# Sheet_1-copy-copy_2026-03-31.net
KiCad netlist of a schematic drawn in Altium Designer
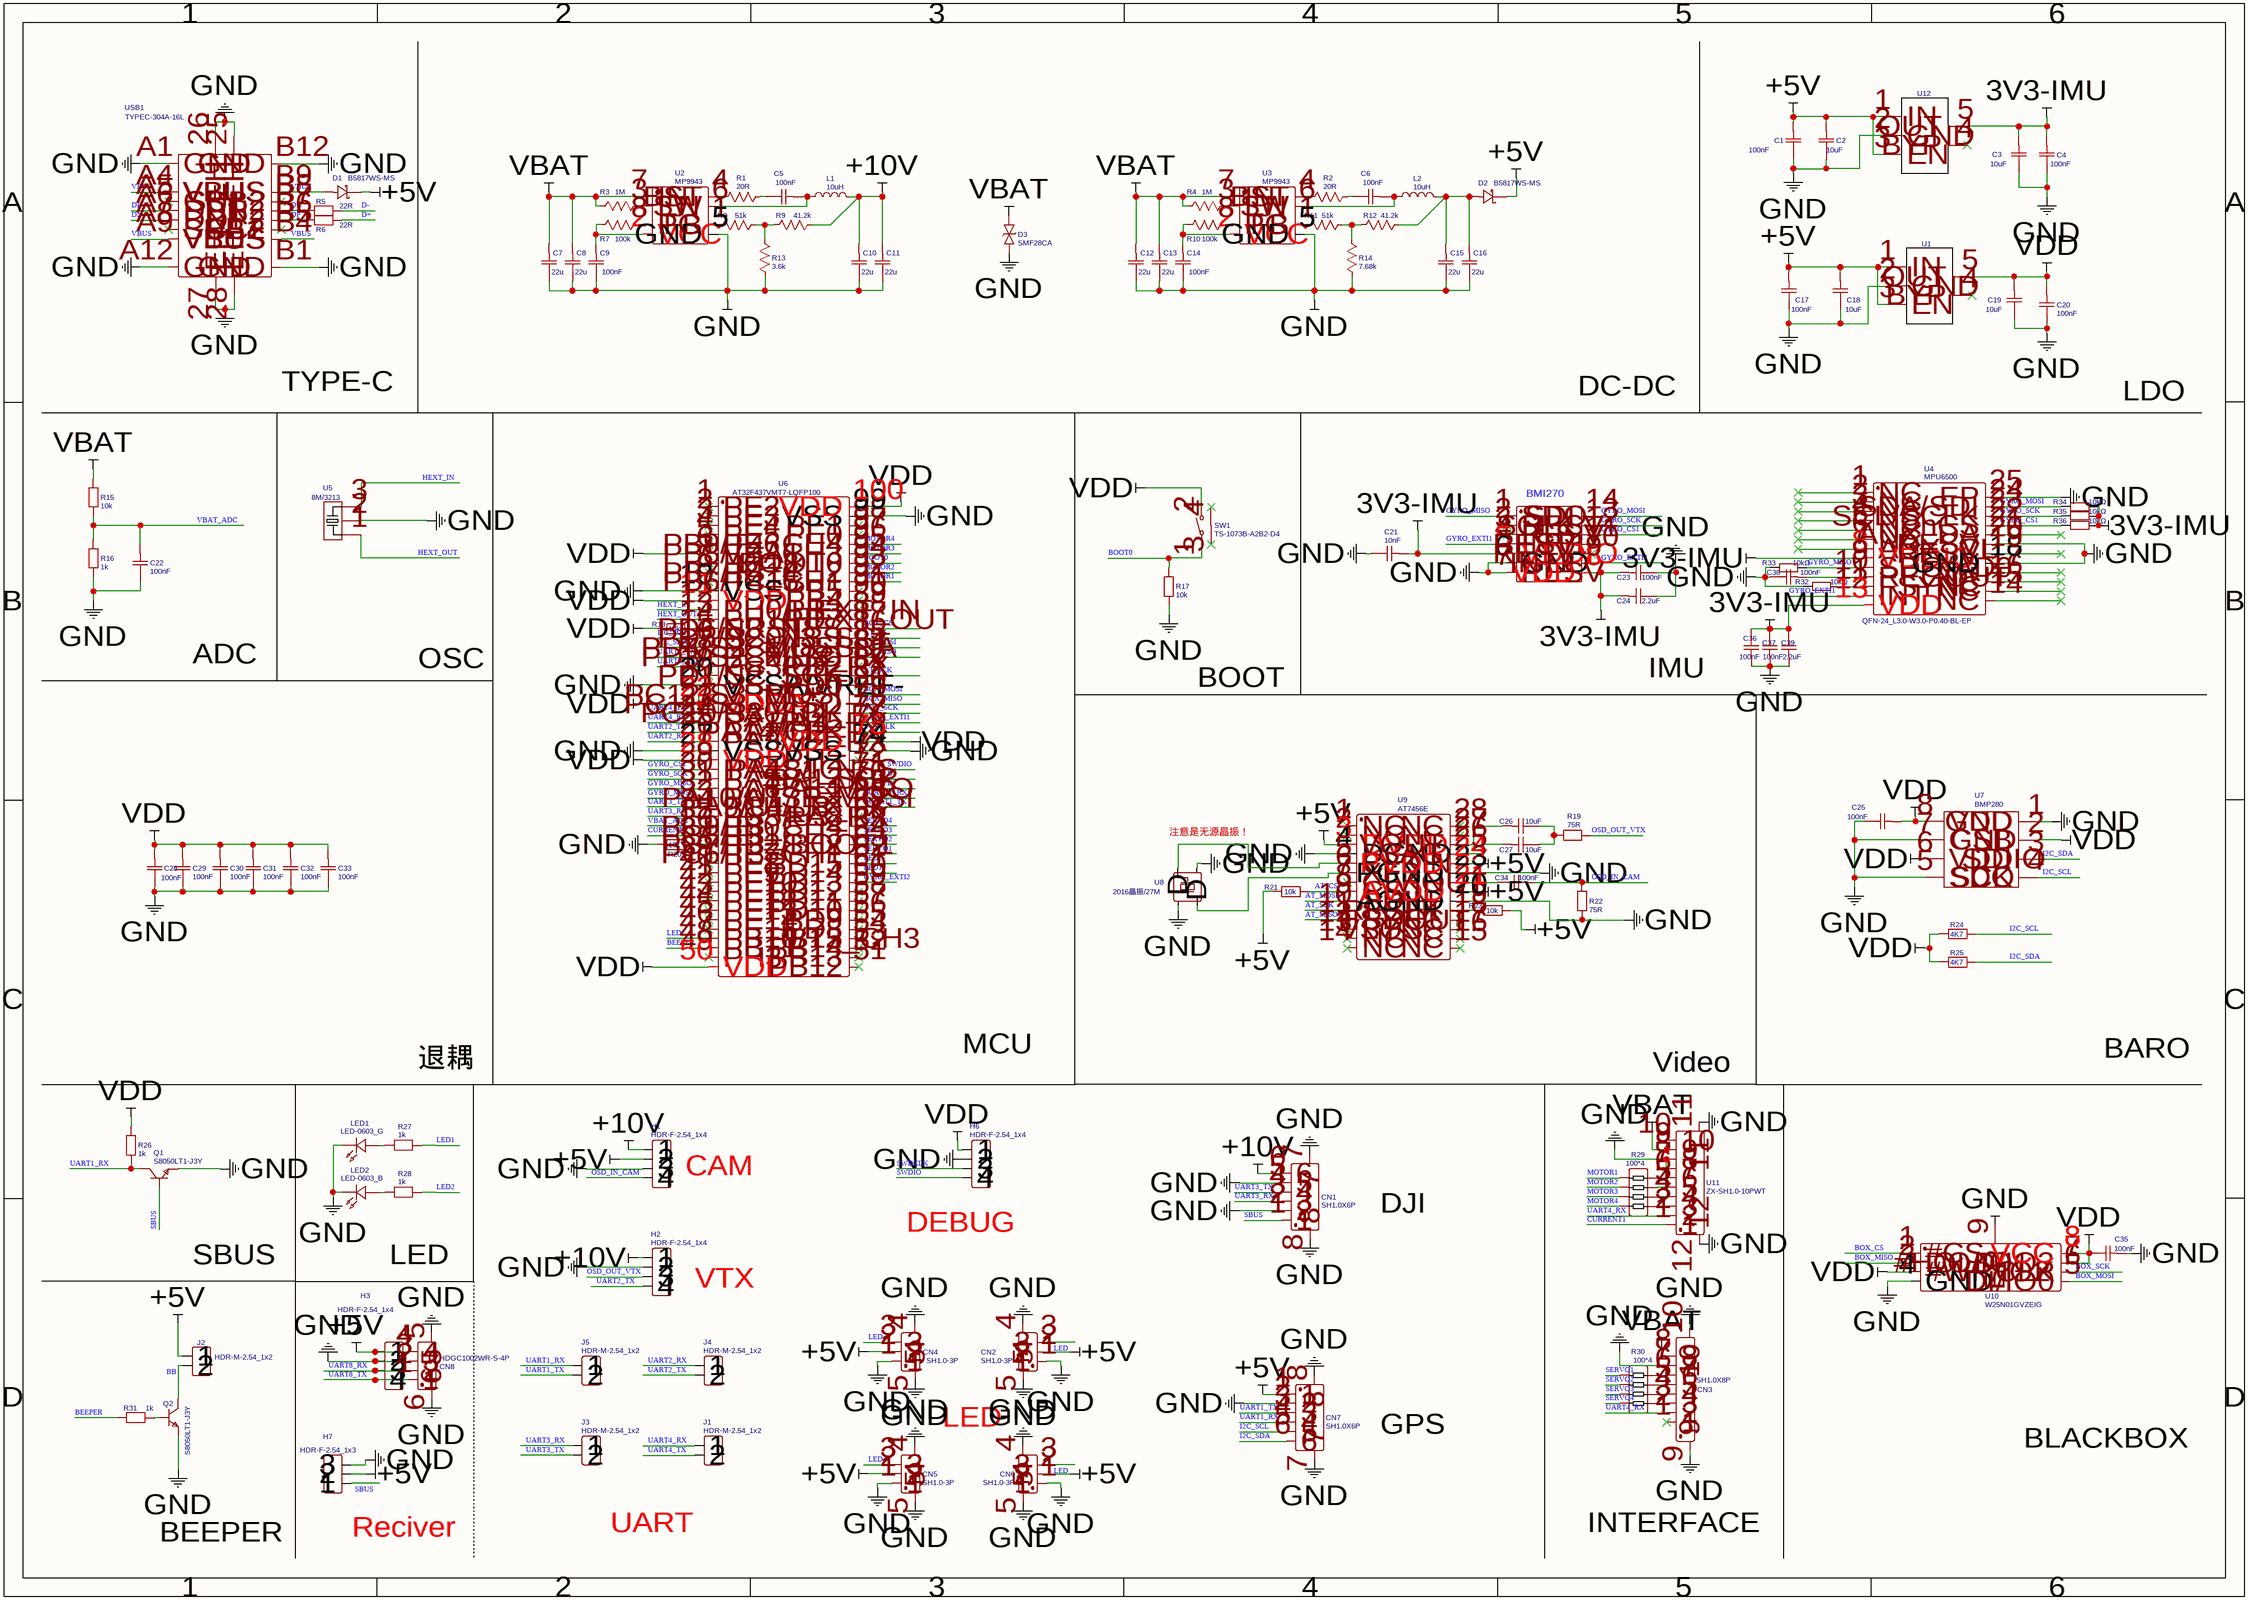
[diagram p0: Sheet_1-copy-copy_2026-03-31.schdoc]

(export (version "E")
  (design (tool "Eeschema 10.0.6"))
  (components
    (comp (ref "C1")
      (value "100nF")
      (fields (field (name "CONTRIBUTOR") "LCEDA_Lib"))
      (libsource (lib "altium-import") (part "root_1_100nF_"))
    )
    (comp (ref "C2")
      (value "10uF")
      (fields (field (name "CONTRIBUTOR") "LCEDA_Lib"))
      (libsource (lib "altium-import") (part "root_1_10uF_"))
    )
    (comp (ref "C3")
      (value "10uF")
      (fields (field (name "CONTRIBUTOR") "LCEDA_Lib"))
      (libsource (lib "altium-import") (part "root_1_10uF_"))
    )
    (comp (ref "C4")
      (value "100nF")
      (fields (field (name "CONTRIBUTOR") "LCEDA_Lib"))
      (libsource (lib "altium-import") (part "root_1_100nF_"))
    )
    (comp (ref "C5")
      (value "100nF")
      (fields (field (name "CONTRIBUTOR") "LCEDA_Lib"))
      (libsource (lib "altium-import") (part "root_0_100nF_"))
    )
    (comp (ref "C6")
      (value "100nF")
      (fields (field (name "CONTRIBUTOR") "LCEDA_Lib"))
      (libsource (lib "altium-import") (part "root_0_100nF_"))
    )
    (comp (ref "C7")
      (value "22u")
      (fields (field (name "CONTRIBUTOR") "LCEDA_Lib"))
      (libsource (lib "altium-import") (part "root_1_22u_"))
    )
    (comp (ref "C8")
      (value "22u")
      (fields (field (name "CONTRIBUTOR") "LCEDA_Lib"))
      (libsource (lib "altium-import") (part "root_1_22u_"))
    )
    (comp (ref "C9")
      (value "100nF")
      (fields (field (name "CONTRIBUTOR") "LCEDA_Lib"))
      (libsource (lib "altium-import") (part "root_1_100nF_"))
    )
    (comp (ref "C10")
      (value "22u")
      (fields (field (name "CONTRIBUTOR") "LCEDA_Lib"))
      (libsource (lib "altium-import") (part "root_1_22u_"))
    )
    (comp (ref "C11")
      (value "22u")
      (fields (field (name "CONTRIBUTOR") "LCEDA_Lib"))
      (libsource (lib "altium-import") (part "root_1_22u_"))
    )
    (comp (ref "C12")
      (value "22u")
      (fields (field (name "CONTRIBUTOR") "LCEDA_Lib"))
      (libsource (lib "altium-import") (part "root_1_22u_"))
    )
    (comp (ref "C13")
      (value "22u")
      (fields (field (name "CONTRIBUTOR") "LCEDA_Lib"))
      (libsource (lib "altium-import") (part "root_1_22u_"))
    )
    (comp (ref "C14")
      (value "100nF")
      (fields (field (name "CONTRIBUTOR") "LCEDA_Lib"))
      (libsource (lib "altium-import") (part "root_1_100nF_"))
    )
    (comp (ref "C15")
      (value "22u")
      (fields (field (name "CONTRIBUTOR") "LCEDA_Lib"))
      (libsource (lib "altium-import") (part "root_1_22u_"))
    )
    (comp (ref "C16")
      (value "22u")
      (fields (field (name "CONTRIBUTOR") "LCEDA_Lib"))
      (libsource (lib "altium-import") (part "root_1_22u_"))
    )
    (comp (ref "C17")
      (value "100nF")
      (fields (field (name "CONTRIBUTOR") "LCEDA_Lib"))
      (libsource (lib "altium-import") (part "root_1_100nF_"))
    )
    (comp (ref "C18")
      (value "10uF")
      (fields (field (name "CONTRIBUTOR") "LCEDA_Lib"))
      (libsource (lib "altium-import") (part "root_1_10uF_"))
    )
    (comp (ref "C19")
      (value "10uF")
      (fields (field (name "CONTRIBUTOR") "LCEDA_Lib"))
      (libsource (lib "altium-import") (part "root_1_10uF_"))
    )
    (comp (ref "C20")
      (value "100nF")
      (fields (field (name "CONTRIBUTOR") "LCEDA_Lib"))
      (libsource (lib "altium-import") (part "root_1_100nF_"))
    )
    (comp (ref "C21")
      (value "10nF")
      (fields (field (name "CONTRIBUTOR") "LCEDA_Lib"))
      (libsource (lib "altium-import") (part "root_0_10nF_"))
    )
    (comp (ref "C22")
      (value "100nF")
      (fields (field (name "CONTRIBUTOR") "LCEDA_Lib"))
      (libsource (lib "altium-import") (part "root_1_100nF_"))
    )
    (comp (ref "C23")
      (value "100nF")
      (fields (field (name "CONTRIBUTOR") "LCEDA_Lib"))
      (libsource (lib "altium-import") (part "root_2_100nF_"))
    )
    (comp (ref "C24")
      (value "2.2uF")
      (fields (field (name "CONTRIBUTOR") "LCEDA_Lib"))
      (libsource (lib "altium-import") (part "root_2_2.2uF_"))
    )
    (comp (ref "C25")
      (value "100nF")
      (fields (field (name "CONTRIBUTOR") "LCEDA_Lib"))
      (libsource (lib "altium-import") (part "root_0_100nF_"))
    )
    (comp (ref "C26")
      (value "10uF")
      (fields (field (name "CONTRIBUTOR") "LCEDA_Lib"))
      (libsource (lib "altium-import") (part "root_2_10uF_"))
    )
    (comp (ref "C27")
      (value "10uF")
      (fields (field (name "CONTRIBUTOR") "LCEDA_Lib"))
      (libsource (lib "altium-import") (part "root_2_10uF_"))
    )
    (comp (ref "C28")
      (value "100nF")
      (fields (field (name "CONTRIBUTOR") "LCEDA_Lib"))
      (libsource (lib "altium-import") (part "root_1_100nF_"))
    )
    (comp (ref "C29")
      (value "100nF")
      (fields (field (name "CONTRIBUTOR") "LCEDA_Lib"))
      (libsource (lib "altium-import") (part "root_1_100nF_"))
    )
    (comp (ref "C30")
      (value "100nF")
      (fields (field (name "CONTRIBUTOR") "LCEDA_Lib"))
      (libsource (lib "altium-import") (part "root_1_100nF_"))
    )
    (comp (ref "C31")
      (value "100nF")
      (fields (field (name "CONTRIBUTOR") "LCEDA_Lib"))
      (libsource (lib "altium-import") (part "root_1_100nF_"))
    )
    (comp (ref "C32")
      (value "100nF")
      (fields (field (name "CONTRIBUTOR") "LCEDA_Lib"))
      (libsource (lib "altium-import") (part "root_1_100nF_"))
    )
    (comp (ref "C33")
      (value "100nF")
      (fields (field (name "CONTRIBUTOR") "LCEDA_Lib"))
      (libsource (lib "altium-import") (part "root_1_100nF_"))
    )
    (comp (ref "C34")
      (value "100nF")
      (fields (field (name "CONTRIBUTOR") "LCEDA_Lib"))
      (libsource (lib "altium-import") (part "root_0_100nF_"))
    )
    (comp (ref "C35")
      (value "100nF")
      (fields (field (name "CONTRIBUTOR") "LCEDA_Lib"))
      (libsource (lib "altium-import") (part "root_0_100nF_"))
    )
    (comp (ref "C36")
      (value "100nF")
      (fields (field (name "CONTRIBUTOR") "LCEDA_Lib"))
      (libsource (lib "altium-import") (part "root_3_100nF_"))
    )
    (comp (ref "C37")
      (value "100nF")
      (fields (field (name "CONTRIBUTOR") "LCEDA_Lib"))
      (libsource (lib "altium-import") (part "root_3_100nF_"))
    )
    (comp (ref "C38")
      (value "100nF")
      (fields (field (name "CONTRIBUTOR") "LCEDA_Lib"))
      (libsource (lib "altium-import") (part "root_0_100nF_"))
    )
    (comp (ref "C39")
      (value "2.2uF")
      (fields (field (name "CONTRIBUTOR") "LCEDA_Lib"))
      (libsource (lib "altium-import") (part "root_3_2.2uF_"))
    )
    (comp (ref "CN1")
      (value "SH1.0X6P")
      (fields
        (field (name "MANUFACTURER") "Megastar(兆星)")
        (field (name "MANUFACTURER PART") "ZX-SH1.0-6PWT")
        (field (name "CONTRIBUTOR") "lcsc")
      )
      (libsource (lib "altium-import") (part "root_0_SH1.0X6P_"))
    )
    (comp (ref "CN2")
      (value "SH1.0-3P")
      (fields
        (field (name "MANUFACTURER") "HDGC(华德共创)")
        (field (name "MANUFACTURER PART") "HDGC1002WR-S-3P")
        (field (name "CONTRIBUTOR") "LCSC")
      )
      (libsource (lib "") (part "root_2_SH1.0-3P__1"))
    )
    (comp (ref "CN3")
      (value "SH1.0X8P")
      (fields (field (name "MANUFACTURER PART") "WAFER_SMT_1.0X8") (field (name "CONTRIBUTOR") "lcsc"))
      (libsource (lib "altium-import") (part "root_0_SH1.0X8P_"))
    )
    (comp (ref "CN4")
      (value "SH1.0-3P")
      (fields
        (field (name "MANUFACTURER") "HDGC(华德共创)")
        (field (name "MANUFACTURER PART") "HDGC1002WR-S-3P")
        (field (name "CONTRIBUTOR") "LCSC")
      )
      (libsource (lib "altium-import") (part "root_2_SH1.0-3P_"))
    )
    (comp (ref "CN5")
      (value "SH1.0-3P")
      (fields
        (field (name "MANUFACTURER") "HDGC(华德共创)")
        (field (name "MANUFACTURER PART") "HDGC1002WR-S-3P")
        (field (name "CONTRIBUTOR") "LCSC")
      )
      (libsource (lib "altium-import") (part "root_0_SH1.0-3P_"))
    )
    (comp (ref "CN6")
      (value "SH1.0-3P")
      (fields
        (field (name "MANUFACTURER") "HDGC(华德共创)")
        (field (name "MANUFACTURER PART") "HDGC1002WR-S-3P")
        (field (name "CONTRIBUTOR") "LCSC")
      )
      (libsource (lib "") (part "root_0_SH1.0-3P__1"))
    )
    (comp (ref "CN7")
      (value "SH1.0X6P")
      (fields
        (field (name "MANUFACTURER") "Megastar(兆星)")
        (field (name "MANUFACTURER PART") "ZX-SH1.0-6PWT")
        (field (name "CONTRIBUTOR") "lcsc")
      )
      (libsource (lib "") (part "root_0_SH1.0X6P__1"))
    )
    (comp (ref "CN8")
      (value "HDGC1002WR-S-4P")
      (fields (field (name "MANUFACTURER") "HDGC(华德共创)") (field (name "CONTRIBUTOR") "LCSC"))
      (libsource (lib "altium-import") (part "root_0_HDGC1002WR-S-4P_"))
    )
    (comp (ref "D1")
      (value "B5817WS-MS")
      (fields (field (name "MANUFACTURER") "MSKSEMI(美森科)") (field (name "CONTRIBUTOR") "LCSC"))
      (libsource (lib "altium-import") (part "root_2_B5817WS-MS_"))
    )
    (comp (ref "D2")
      (value "B5817WS-MS")
      (fields (field (name "MANUFACTURER") "MSKSEMI(美森科)") (field (name "CONTRIBUTOR") "LCSC"))
      (libsource (lib "altium-import") (part "root_2_B5817WS-MS_"))
    )
    (comp (ref "D3")
      (value "SMF28CA")
      (fields (field (name "MANUFACTURER") "AnBon(安邦)") (field (name "CONTRIBUTOR") "LCSC"))
      (libsource (lib "altium-import") (part "root_3_SMF28CA_"))
    )
    (comp (ref "H1")
      (value "HDR-F-2.54_1x4")
      (fields (field (name "CONTRIBUTOR") "LCEDA_Lib"))
      (libsource (lib "altium-import") (part "root_0_HDR-F-2.54_1x4_"))
    )
    (comp (ref "H2")
      (value "HDR-F-2.54_1x4")
      (fields (field (name "CONTRIBUTOR") "LCEDA_Lib"))
      (libsource (lib "altium-import") (part "root_0_HDR-F-2.54_1x4_"))
    )
    (comp (ref "H3")
      (value "HDR-F-2.54_1x4")
      (fields (field (name "CONTRIBUTOR") "LCEDA_Lib"))
      (libsource (lib "altium-import") (part "root_0_HDR-F-2.54_1x4_"))
    )
    (comp (ref "H6")
      (value "HDR-F-2.54_1x4")
      (fields (field (name "CONTRIBUTOR") "LCEDA_Lib"))
      (libsource (lib "altium-import") (part "root_0_HDR-F-2.54_1x4_"))
    )
    (comp (ref "H7")
      (value "HDR-F-2.54_1x3")
      (fields (field (name "CONTRIBUTOR") "LCEDA_Lib"))
      (libsource (lib "altium-import") (part "root_2_HDR-F-2.54_1x3_"))
    )
    (comp (ref "J1")
      (value "HDR-M-2.54_1x2")
      (fields (field (name "CONTRIBUTOR") "LCEDA_Lib"))
      (libsource (lib "altium-import") (part "root_0_HDR-M-2.54_1x2_"))
    )
    (comp (ref "J2")
      (value "HDR-M-2.54_1x2")
      (fields (field (name "CONTRIBUTOR") "LCEDA_Lib"))
      (libsource (lib "altium-import") (part "root_0_HDR-M-2.54_1x2_"))
    )
    (comp (ref "J3")
      (value "HDR-M-2.54_1x2")
      (fields (field (name "CONTRIBUTOR") "LCEDA_Lib"))
      (libsource (lib "altium-import") (part "root_0_HDR-M-2.54_1x2_"))
    )
    (comp (ref "J4")
      (value "HDR-M-2.54_1x2")
      (fields (field (name "CONTRIBUTOR") "LCEDA_Lib"))
      (libsource (lib "altium-import") (part "root_0_HDR-M-2.54_1x2_"))
    )
    (comp (ref "J5")
      (value "HDR-M-2.54_1x2")
      (fields (field (name "CONTRIBUTOR") "LCEDA_Lib"))
      (libsource (lib "altium-import") (part "root_0_HDR-M-2.54_1x2_"))
    )
    (comp (ref "L1")
      (value "10uH")
      (fields
        (field (name "MANUFACTURER") "EMTEK")
        (field (name "MANUFACTURER PART") "PHC0420-100M-T")
        (field (name "CONTRIBUTOR") "LCSC")
      )
      (libsource (lib "altium-import") (part "root_0_10uH_"))
    )
    (comp (ref "L2")
      (value "10uH")
      (fields
        (field (name "MANUFACTURER") "EMTEK")
        (field (name "MANUFACTURER PART") "PHC0420-100M-T")
        (field (name "CONTRIBUTOR") "LCSC")
      )
      (libsource (lib "altium-import") (part "root_0_10uH_"))
    )
    (comp (ref "LED1")
      (value "LED-0603_G")
      (fields
        (field (name "MANUFACTURER") "EVERLIGHT(台湾亿光)")
        (field (name "MANUFACTURER PART") "19-217/GHC-YR1S2/3T")
        (field (name "CONTRIBUTOR") "LCEDA_Lib")
      )
      (libsource (lib "altium-import") (part "root_2_LED-0603_G_"))
    )
    (comp (ref "LED2")
      (value "LED-0603_B")
      (fields
        (field (name "MANUFACTURER") "EVERLIGHT(台湾亿光)")
        (field (name "MANUFACTURER PART") "19-217/BHC-ZL1M2RY/3T")
        (field (name "CONTRIBUTOR") "LCEDA_01")
      )
      (libsource (lib "altium-import") (part "root_2_LED-0603_B_"))
    )
    (comp (ref "Q1")
      (value "S8050LT1-J3Y")
      (fields (field (name "MANUFACTURER") "FH(风华)") (field (name "CONTRIBUTOR") "lcsc"))
      (libsource (lib "altium-import") (part "root_1_S8050LT1-J3Y_"))
    )
    (comp (ref "Q2")
      (value "S8050LT1-J3Y")
      (fields (field (name "MANUFACTURER") "FH(风华)") (field (name "CONTRIBUTOR") "lcsc"))
      (libsource (lib "altium-import") (part "root_0_S8050LT1-J3Y_"))
    )
    (comp (ref "R1")
      (value "20R")
      (fields (field (name "CONTRIBUTOR") "LCEDA_Lib"))
      (libsource (lib "altium-import") (part "root_0_20R_"))
    )
    (comp (ref "R2")
      (value "20R")
      (fields (field (name "CONTRIBUTOR") "LCEDA_Lib"))
      (libsource (lib "altium-import") (part "root_0_20R_"))
    )
    (comp (ref "R3")
      (value "1M")
      (fields (field (name "CONTRIBUTOR") "LCEDA_Lib"))
      (libsource (lib "altium-import") (part "root_2_1M_"))
    )
    (comp (ref "R4")
      (value "1M")
      (fields (field (name "CONTRIBUTOR") "LCEDA_Lib"))
      (libsource (lib "altium-import") (part "root_2_1M_"))
    )
    (comp (ref "R5")
      (value "22R")
      (fields (field (name "CONTRIBUTOR") "LCEDA_Lib"))
      (libsource (lib "altium-import") (part "root_0_22R_"))
    )
    (comp (ref "R6")
      (value "22R")
      (fields (field (name "CONTRIBUTOR") "LCEDA_Lib"))
      (libsource (lib "altium-import") (part "root_0_22R_"))
    )
    (comp (ref "R7")
      (value "100k")
      (fields (field (name "CONTRIBUTOR") "LCEDA_Lib"))
      (libsource (lib "altium-import") (part "root_0_100k_"))
    )
    (comp (ref "R8")
      (value "51k")
      (fields (field (name "CONTRIBUTOR") "LCEDA_Lib"))
      (libsource (lib "altium-import") (part "root_0_51k_"))
    )
    (comp (ref "R9")
      (value "41.2k")
      (fields (field (name "CONTRIBUTOR") "LCEDA_Lib"))
      (libsource (lib "altium-import") (part "root_0_41.2k_"))
    )
    (comp (ref "R10")
      (value "100k")
      (fields (field (name "CONTRIBUTOR") "LCEDA_Lib"))
      (libsource (lib "altium-import") (part "root_0_100k_"))
    )
    (comp (ref "R11")
      (value "51k")
      (fields (field (name "CONTRIBUTOR") "LCEDA_Lib"))
      (libsource (lib "altium-import") (part "root_0_51k_"))
    )
    (comp (ref "R12")
      (value "41.2k")
      (fields (field (name "CONTRIBUTOR") "LCEDA_Lib"))
      (libsource (lib "altium-import") (part "root_0_41.2k_"))
    )
    (comp (ref "R13")
      (value "3.6k")
      (fields (field (name "CONTRIBUTOR") "LCEDA_Lib"))
      (libsource (lib "altium-import") (part "root_1_3.6k_"))
    )
    (comp (ref "R14")
      (value "7.68k")
      (fields (field (name "CONTRIBUTOR") "LCEDA_Lib"))
      (libsource (lib "altium-import") (part "root_1_7.68k_"))
    )
    (comp (ref "R15")
      (value "10k")
      (fields (field (name "CONTRIBUTOR") "LCEDA_Lib"))
      (libsource (lib "altium-import") (part "root_1_10k_"))
    )
    (comp (ref "R16")
      (value "1k")
      (fields (field (name "CONTRIBUTOR") "LCEDA_Lib"))
      (libsource (lib "altium-import") (part "root_1_1k_"))
    )
    (comp (ref "R17")
      (value "10k")
      (fields (field (name "CONTRIBUTOR") "LCEDA_Lib"))
      (libsource (lib "altium-import") (part "root_3_10k_"))
    )
    (comp (ref "R18")
      (value "10k")
      (fields (field (name "CONTRIBUTOR") "LCEDA_Lib"))
      (libsource (lib "altium-import") (part "root_2_10k_"))
    )
    (comp (ref "R19")
      (value "75R")
      (fields (field (name "CONTRIBUTOR") "LCEDA_Lib"))
      (libsource (lib "altium-import") (part "root_0_75R_"))
    )
    (comp (ref "R20")
      (value "10k")
      (fields (field (name "CONTRIBUTOR") "LCEDA_Lib"))
      (libsource (lib "altium-import") (part "root_0_10k_"))
    )
    (comp (ref "R21")
      (value "10k")
      (fields (field (name "CONTRIBUTOR") "LCEDA_Lib"))
      (libsource (lib "altium-import") (part "root_0_10k_"))
    )
    (comp (ref "R22")
      (value "75R")
      (fields (field (name "CONTRIBUTOR") "LCEDA_Lib"))
      (libsource (lib "altium-import") (part "root_1_75R_"))
    )
    (comp (ref "R23")
      (value "10k")
      (fields (field (name "CONTRIBUTOR") "LCEDA_Lib"))
      (libsource (lib "altium-import") (part "root_0_10k_"))
    )
    (comp (ref "R24")
      (value "4K7")
      (fields (field (name "CONTRIBUTOR") "LCEDA_Lib"))
      (libsource (lib "altium-import") (part "root_2_4K7_"))
    )
    (comp (ref "R25")
      (value "4K7")
      (fields (field (name "CONTRIBUTOR") "LCEDA_Lib"))
      (libsource (lib "altium-import") (part "root_2_4K7_"))
    )
    (comp (ref "R26")
      (value "1k")
      (fields (field (name "CONTRIBUTOR") "LCEDA_Lib"))
      (libsource (lib "altium-import") (part "root_1_1k_"))
    )
    (comp (ref "R27")
      (value "1k")
      (fields (field (name "CONTRIBUTOR") "LCEDA_Lib"))
      (libsource (lib "altium-import") (part "root_0_1k_"))
    )
    (comp (ref "R28")
      (value "1k")
      (fields (field (name "CONTRIBUTOR") "LCEDA_Lib"))
      (libsource (lib "altium-import") (part "root_0_1k_"))
    )
    (comp (ref "R29")
      (value "100*4")
      (fields
        (field (name "MANUFACTURER") "UNI-ROYAL(厚声)")
        (field (name "MANUFACTURER PART") "4D02WGF1002TCE")
        (field (name "CONTRIBUTOR") "LCSC")
      )
      (libsource (lib "altium-import") (part "root_2_100*4_"))
    )
    (comp (ref "R30")
      (value "100*4")
      (fields
        (field (name "MANUFACTURER") "UNI-ROYAL(厚声)")
        (field (name "MANUFACTURER PART") "4D02WGF1002TCE")
        (field (name "CONTRIBUTOR") "LCSC")
      )
      (libsource (lib "altium-import") (part "root_2_100*4_"))
    )
    (comp (ref "R31")
      (value "1k")
      (fields (field (name "CONTRIBUTOR") "LCEDA_Lib"))
      (libsource (lib "altium-import") (part "root_0_1k_"))
    )
    (comp (ref "R32")
      (value "10kΩ")
      (fields (field (name "MANUFACTURER") "YAGEO(国巨)") (field (name "MANUFACTURER PART") "RC0402FR-0710KL"))
      (libsource (lib "altium-import") (part "root_0_10kΩ_"))
    )
    (comp (ref "R33")
      (value "10kΩ")
      (fields (field (name "MANUFACTURER") "YAGEO(国巨)") (field (name "MANUFACTURER PART") "RC0402FR-0710KL"))
      (libsource (lib "altium-import") (part "root_0_10kΩ_"))
    )
    (comp (ref "R34")
      (value "10kΩ")
      (fields (field (name "MANUFACTURER") "YAGEO(国巨)") (field (name "MANUFACTURER PART") "RC0402FR-0710KL"))
      (libsource (lib "altium-import") (part "root_0_10kΩ_"))
    )
    (comp (ref "R35")
      (value "10kΩ")
      (fields (field (name "MANUFACTURER") "YAGEO(国巨)") (field (name "MANUFACTURER PART") "RC0402FR-0710KL"))
      (libsource (lib "altium-import") (part "root_0_10kΩ_"))
    )
    (comp (ref "R36")
      (value "10kΩ")
      (fields (field (name "MANUFACTURER") "YAGEO(国巨)") (field (name "MANUFACTURER PART") "RC0402FR-0710KL"))
      (libsource (lib "altium-import") (part "root_0_10kΩ_"))
    )
    (comp (ref "SDO1")
      (value "BMI270")
      (fields (field (name "CONTRIBUTOR") "SPRain"))
      (libsource (lib "altium-import") (part "root_0_BMI270_"))
    )
    (comp (ref "SW1")
      (value "TS-1073B-A2B2-D4")
      (fields (field (name "MANUFACTURER") "Yuandi(元迪)") (field (name "CONTRIBUTOR") "LCSC"))
      (libsource (lib "altium-import") (part "root_1_TS-1073B-A2B2-D4_"))
    )
    (comp (ref "U1")
      (value "SPX3819M5-L-3-3/TR")
      (fields (field (name "MANUFACTURER") "MaxLinear(迈凌)"))
      (libsource (lib "altium-import") (part "root_0_SPX3819M5-L-3-3/TR_"))
    )
    (comp (ref "U2")
      (value "MP9943")
      (fields (field (name "CONTRIBUTOR") "jeasyn"))
      (libsource (lib "altium-import") (part "root_0_MP9943_"))
    )
    (comp (ref "U3")
      (value "MP9943")
      (fields (field (name "CONTRIBUTOR") "jeasyn"))
      (libsource (lib "altium-import") (part "root_0_MP9943_"))
    )
    (comp (ref "U4")
      (value "MPU6500")
      (fields
        (field (name "MANUFACTURER") "TDK InvenSense(应美盛)")
        (field (name "MANUFACTURER PART") "MPU-6500")
      )
      (libsource (lib "altium-import") (part "root_0_MPU6500_"))
    )
    (comp (ref "U5")
      (value "8M/3213")
      (fields (field (name "CONTRIBUTOR") "5_6956"))
      (libsource (lib "altium-import") (part "root_1_8M/3213_"))
    )
    (comp (ref "U6")
      (value "AT32F437VMT7-LQFP100")
      (fields
        (field (name "MANUFACTURER") "ARTERY（雅特力）")
        (field (name "MANUFACTURER PART") "AT32F435VMT7")
        (field (name "CONTRIBUTOR") "lcsc")
      )
      (libsource (lib "altium-import") (part "root_0_AT32F437VMT7-LQFP100_"))
    )
    (comp (ref "U7")
      (value "BMP280")
      (fields (field (name "MANUFACTURER") "Bosch"))
      (libsource (lib "altium-import") (part "root_0_BMP280_"))
    )
    (comp (ref "U8")
      (value "2016晶振/27M")
      (fields (field (name "CONTRIBUTOR") "jimssa"))
      (libsource (lib "altium-import") (part "root_2_2016晶振/27M_"))
    )
    (comp (ref "U9")
      (value "AT7456E")
      (fields (field (name "MANUFACTURER") "ZHONGKEWEI"))
      (libsource (lib "altium-import") (part "root_0_AT7456E_"))
    )
    (comp (ref "U10")
      (value "W25N01GVZEIG")
      (fields (field (name "MANUFACTURER") "Winbond Elec") (field (name "CONTRIBUTOR") "SudoMaker"))
      (libsource (lib "altium-import") (part "root_0_W25N01GVZEIG_"))
    )
    (comp (ref "U11")
      (value "ZX-SH1.0-10PWT")
      (fields (field (name "MANUFACTURER") "Megastar(兆星)") (field (name "CONTRIBUTOR") "lcsc"))
      (libsource (lib "altium-import") (part "root_0_ZX-SH1.0-10PWT_"))
    )
    (comp (ref "U12")
      (value "SPX3819M5-L-3-3/TR")
      (fields (field (name "MANUFACTURER") "MaxLinear(迈凌)"))
      (libsource (lib "altium-import") (part "root_0_SPX3819M5-L-3-3/TR_"))
    )
    (comp (ref "USB1")
      (value "TYPEC-304A-16L")
      (fields
        (field (name "MANUFACTURER") "XUNPU(讯普)")
        (field (name "MANUFACTURER PART") "TYPEC-304A-ACP16L")
        (field (name "CONTRIBUTOR") "LCSC")
      )
      (libsource (lib "altium-import") (part "root_0_TYPEC-304A-16L_"))
    )
  )
  (nets
    (net (code "1") (name "+5V") (class "Default")
      (node (ref "C1") (pin "2") (pinfunction "2_2") (pintype "passive"))
      (node (ref "C17") (pin "2") (pinfunction "2_2") (pintype "passive"))
      (node (ref "C18") (pin "2") (pinfunction "2_2") (pintype "passive"))
      (node (ref "C2") (pin "2") (pinfunction "2_2") (pintype "passive"))
      (node (ref "CN2") (pin "2") (pinfunction "2_2") (pintype "passive"))
      (node (ref "CN4") (pin "2") (pinfunction "2_2") (pintype "passive"))
      (node (ref "CN5") (pin "2") (pinfunction "2_2") (pintype "passive"))
      (node (ref "CN6") (pin "2") (pinfunction "2_2") (pintype "passive"))
      (node (ref "CN7") (pin "1") (pinfunction "1_1") (pintype "passive"))
      (node (ref "CN8") (pin "4") (pinfunction "4_4") (pintype "passive"))
      (node (ref "D1") (pin "2") (pinfunction "K_2") (pintype "passive"))
      (node (ref "D2") (pin "2") (pinfunction "K_2") (pintype "passive"))
      (node (ref "H1") (pin "2") (pinfunction "2_2") (pintype "passive"))
      (node (ref "H3") (pin "1") (pinfunction "1_1") (pintype "passive"))
      (node (ref "H7") (pin "2") (pinfunction "2_2") (pintype "passive"))
      (node (ref "J2") (pin "1") (pinfunction "1_1") (pintype "passive"))
      (node (ref "R21") (pin "1") (pinfunction "1_1") (pintype "passive"))
      (node (ref "R23") (pin "2") (pinfunction "2_2") (pintype "passive"))
      (node (ref "U1") (pin "1") (pinfunction "IN_1") (pintype "passive"))
      (node (ref "U1") (pin "3") (pinfunction "EN_3") (pintype "passive"))
      (node (ref "U12") (pin "1") (pinfunction "IN_1") (pintype "passive"))
      (node (ref "U12") (pin "3") (pinfunction "EN_3") (pintype "passive"))
      (node (ref "U9") (pin "21") (pinfunction "AVDD_21") (pintype "passive"))
      (node (ref "U9") (pin "24") (pinfunction "PVDD_24") (pintype "passive"))
      (node (ref "U9") (pin "3") (pinfunction "DVDD_3") (pintype "passive"))
    )
    (net (code "2") (name "+10V") (class "Default")
      (node (ref "C10") (pin "2") (pinfunction "2_2") (pintype "passive"))
      (node (ref "C11") (pin "2") (pinfunction "2_2") (pintype "passive"))
      (node (ref "CN1") (pin "6") (pinfunction "6_6") (pintype "passive"))
      (node (ref "H1") (pin "1") (pinfunction "1_1") (pintype "passive"))
      (node (ref "H2") (pin "1") (pinfunction "1_1") (pintype "passive"))
      (node (ref "L1") (pin "2") (pinfunction "2_2") (pintype "passive"))
      (node (ref "R9") (pin "2") (pinfunction "2_2") (pintype "passive"))
    )
    (net (code "3") (name "/AT_CS") (class "Default")
      (node (ref "R21") (pin "2") (pinfunction "2_2") (pintype "passive"))
      (node (ref "U6") (pin "86") (pinfunction "PD5/S2_NSS_86") (pintype "passive"))
      (node (ref "U9") (pin "8") (pinfunction "CS_8") (pintype "passive"))
    )
    (net (code "4") (name "/AT_MISO") (class "Default")
      (node (ref "U6") (pin "84") (pinfunction "PD3/S2_MISO_84") (pintype "passive"))
      (node (ref "U9") (pin "11") (pinfunction "SDOUT_11") (pintype "passive"))
    )
    (net (code "5") (name "/AT_MOSI") (class "Default")
      (node (ref "U6") (pin "85") (pinfunction "PD4/S2_MOSI_85") (pintype "passive"))
      (node (ref "U9") (pin "9") (pinfunction "SDIN_9") (pintype "passive"))
    )
    (net (code "6") (name "/AT_SCK") (class "Default")
      (node (ref "U6") (pin "82") (pinfunction "PD1/S2_SCK_82") (pintype "passive"))
      (node (ref "U9") (pin "10") (pinfunction "SCLK_10") (pintype "passive"))
    )
    (net (code "7") (name "/BB") (class "Default")
      (node (ref "J2") (pin "2") (pinfunction "2_2") (pintype "passive"))
      (node (ref "Q2") (pin "3") (pinfunction "3_3") (pintype "passive"))
    )
    (net (code "8") (name "/BEEPER") (class "Default")
      (node (ref "R31") (pin "1") (pinfunction "1_1") (pintype "passive"))
      (node (ref "U6") (pin "48") (pinfunction "PB11_48") (pintype "passive"))
    )
    (net (code "9") (name "/BOOT0") (class "Default")
      (node (ref "R17") (pin "1") (pinfunction "1_1") (pintype "passive"))
      (node (ref "SW1") (pin "1") (pinfunction "1_1") (pintype "passive"))
      (node (ref "U6") (pin "94") (pinfunction "BOOT0_94") (pintype "passive"))
    )
    (net (code "10") (name "/BOX_CS") (class "Default")
      (node (ref "U10") (pin "1") (pinfunction "#CS_1") (pintype "passive"))
      (node (ref "U6") (pin "87") (pinfunction "PD6/S3_NSS_87") (pintype "passive"))
    )
    (net (code "11") (name "/BOX_MISO") (class "Default")
      (node (ref "U10") (pin "2") (pinfunction "DO/IO1_2") (pintype "passive"))
      (node (ref "U6") (pin "79") (pinfunction "PC11/S3_MISO_79") (pintype "passive"))
    )
    (net (code "12") (name "/BOX_MOSI") (class "Default")
      (node (ref "U10") (pin "5") (pinfunction "DI/IO0_5") (pintype "passive"))
      (node (ref "U6") (pin "80") (pinfunction "PC12/S3_MOSI_80") (pintype "passive"))
    )
    (net (code "13") (name "/BOX_SCK") (class "Default")
      (node (ref "U10") (pin "6") (pinfunction "CLK_6") (pintype "passive"))
      (node (ref "U6") (pin "78") (pinfunction "PC10/S3_SCK_78") (pintype "passive"))
    )
    (net (code "14") (name "/CURRENT1") (class "Default")
      (node (ref "U11") (pin "1") (pinfunction "1_1") (pintype "passive"))
      (node (ref "U6") (pin "36") (pinfunction "PB1_36") (pintype "passive"))
    )
    (net (code "15") (name "/D+") (class "Default")
      (node (ref "R6") (pin "2") (pinfunction "2_2") (pintype "passive"))
      (node (ref "U6") (pin "71") (pinfunction "PA12_71") (pintype "passive"))
    )
    (net (code "16") (name "/D-") (class "Default")
      (node (ref "R5") (pin "2") (pinfunction "2_2") (pintype "passive"))
      (node (ref "U6") (pin "70") (pinfunction "PA11_70") (pintype "passive"))
    )
    (net (code "17") (name "/DN") (class "Default")
      (node (ref "R5") (pin "1") (pinfunction "1_1") (pintype "passive"))
      (node (ref "USB1") (pin "A7") (pinfunction "DN1_A7") (pintype "passive"))
      (node (ref "USB1") (pin "B7") (pinfunction "DN2_B7") (pintype "passive"))
    )
    (net (code "18") (name "/DP") (class "Default")
      (node (ref "R6") (pin "1") (pinfunction "1_1") (pintype "passive"))
      (node (ref "USB1") (pin "A6") (pinfunction "DP1_A6") (pintype "passive"))
      (node (ref "USB1") (pin "B6") (pinfunction "DP2_B6") (pintype "passive"))
    )
    (net (code "19") (name "/GYRO_CS1") (class "Default")
      (node (ref "R36") (pin "1") (pinfunction "1_1") (pintype "passive"))
      (node (ref "SDO1") (pin "12") (pinfunction "CS_12") (pintype "passive"))
      (node (ref "U4") (pin "22") (pinfunction "nCS_22") (pintype "passive"))
      (node (ref "U6") (pin "29") (pinfunction "PA~{4}S1_NSS_29") (pintype "passive"))
    )
    (net (code "20") (name "/GYRO_EXTI1") (class "Default")
      (node (ref "SDO1") (pin "4") (pinfunction "INT1_4") (pintype "passive"))
      (node (ref "U4") (pin "12") (pinfunction "INT_12") (pintype "passive"))
      (node (ref "U6") (pin "77") (pinfunction "PA15_77") (pintype "passive"))
    )
    (net (code "21") (name "/GYRO_EXTI2") (class "Default")
      (node (ref "SDO1") (pin "9") (pinfunction "INT2_9") (pintype "passive"))
      (node (ref "U6") (pin "60") (pinfunction "PD13_60") (pintype "passive"))
    )
    (net (code "22") (name "/GYRO_MISO") (class "Default")
      (node (ref "R33") (pin "2") (pinfunction "2_2") (pintype "passive"))
      (node (ref "SDO1") (pin "1") (pinfunction "SDO_1") (pintype "passive"))
      (node (ref "U4") (pin "9") (pinfunction "SDO/AD0_9") (pintype "passive"))
      (node (ref "U6") (pin "31") (pinfunction "PA~{6}S1_MISO_31") (pintype "passive"))
    )
    (net (code "23") (name "/GYRO_MOSI") (class "Default")
      (node (ref "R34") (pin "1") (pinfunction "1_1") (pintype "passive"))
      (node (ref "SDO1") (pin "14") (pinfunction "SDI_14") (pintype "passive"))
      (node (ref "U4") (pin "24") (pinfunction "SDA/SDI_24") (pintype "passive"))
      (node (ref "U6") (pin "32") (pinfunction "PA~{7}S1_MOSI_32") (pintype "passive"))
    )
    (net (code "24") (name "/GYRO_SCK") (class "Default")
      (node (ref "R35") (pin "1") (pinfunction "1_1") (pintype "passive"))
      (node (ref "SDO1") (pin "13") (pinfunction "SCLK_13") (pintype "passive"))
      (node (ref "U4") (pin "23") (pinfunction "SCL/SCLK_23") (pintype "passive"))
      (node (ref "U6") (pin "30") (pinfunction "PA~{5}S1_SCK_30") (pintype "passive"))
    )
    (net (code "25") (name "/HEXT_IN") (class "Default")
      (node (ref "U5") (pin "3") (pinfunction "3_3") (pintype "passive"))
      (node (ref "U6") (pin "12") (pinfunction "PH0/HEXT_IN_12") (pintype "passive"))
    )
    (net (code "26") (name "/HEXT_OUT") (class "Default")
      (node (ref "U5") (pin "1") (pinfunction "1_1") (pintype "passive"))
      (node (ref "U6") (pin "13") (pinfunction "PH1/HEXT_OUT_13") (pintype "passive"))
    )
    (net (code "27") (name "/I2C_SCL") (class "Default")
      (node (ref "CN7") (pin "5") (pinfunction "5_5") (pintype "passive"))
      (node (ref "R24") (pin "1") (pinfunction "1_1") (pintype "passive"))
      (node (ref "U6") (pin "15") (pinfunction "PC0/I3_SCL_15") (pintype "passive"))
      (node (ref "U7") (pin "4") (pinfunction "SCK_4") (pintype "passive"))
    )
    (net (code "28") (name "/I2C_SDA") (class "Default")
      (node (ref "CN7") (pin "6") (pinfunction "6_6") (pintype "passive"))
      (node (ref "R25") (pin "1") (pinfunction "1_1") (pintype "passive"))
      (node (ref "U6") (pin "16") (pinfunction "PC1/I3_SDA_16") (pintype "passive"))
      (node (ref "U7") (pin "3") (pinfunction "SDI_3") (pintype "passive"))
    )
    (net (code "29") (name "/LED") (class "Default")
      (node (ref "CN2") (pin "3") (pinfunction "3_3") (pintype "passive"))
      (node (ref "CN4") (pin "3") (pinfunction "3_3") (pintype "passive"))
      (node (ref "CN5") (pin "3") (pinfunction "3_3") (pintype "passive"))
      (node (ref "CN6") (pin "3") (pinfunction "3_3") (pintype "passive"))
      (node (ref "U6") (pin "47") (pinfunction "PB10/T2_CH3_47") (pintype "passive"))
    )
    (net (code "30") (name "/LED1") (class "Default")
      (node (ref "R27") (pin "2") (pinfunction "2_2") (pintype "passive"))
      (node (ref "U6") (pin "61") (pinfunction "PD14_61") (pintype "passive"))
    )
    (net (code "31") (name "/LED2") (class "Default")
      (node (ref "R28") (pin "2") (pinfunction "2_2") (pintype "passive"))
      (node (ref "U6") (pin "62") (pinfunction "PD15_62") (pintype "passive"))
    )
    (net (code "32") (name "/MOTOR1") (class "Default")
      (node (ref "R29") (pin "4") (pinfunction "4_4") (pintype "passive"))
      (node (ref "U6") (pin "92") (pinfunction "PB6/T4_CH1_92") (pintype "passive"))
    )
    (net (code "33") (name "/MOTOR2") (class "Default")
      (node (ref "R29") (pin "3") (pinfunction "3_3") (pintype "passive"))
      (node (ref "U6") (pin "93") (pinfunction "PB7/T4_CH2_93") (pintype "passive"))
    )
    (net (code "34") (name "/MOTOR3") (class "Default")
      (node (ref "R29") (pin "2") (pinfunction "2_2") (pintype "passive"))
      (node (ref "U6") (pin "95") (pinfunction "PB8/T4_CH3_95") (pintype "passive"))
    )
    (net (code "35") (name "/MOTOR4") (class "Default")
      (node (ref "R29") (pin "1") (pinfunction "1_1") (pintype "passive"))
      (node (ref "U6") (pin "96") (pinfunction "PB9/T4_CH4_96") (pintype "passive"))
    )
    (net (code "36") (name "/OSD_IN_CAM") (class "Default")
      (node (ref "C34") (pin "2") (pinfunction "2_2") (pintype "passive"))
      (node (ref "H1") (pin "4") (pinfunction "4_4") (pintype "passive"))
      (node (ref "R22") (pin "2") (pinfunction "2_2") (pintype "passive"))
    )
    (net (code "37") (name "/OSD_OUT_VTX") (class "Default")
      (node (ref "H2") (pin "3") (pinfunction "3_3") (pintype "passive"))
      (node (ref "R19") (pin "2") (pinfunction "2_2") (pintype "passive"))
    )
    (net (code "38") (name "/SBUS") (class "Default")
      (node (ref "CN1") (pin "1") (pinfunction "1_1") (pintype "passive"))
      (node (ref "H7") (pin "1") (pinfunction "1_1") (pintype "passive"))
      (node (ref "Q1") (pin "1") (pinfunction "1_1") (pintype "passive"))
    )
    (net (code "39") (name "/SERVO1") (class "Default")
      (node (ref "R30") (pin "4") (pinfunction "4_4") (pintype "passive"))
      (node (ref "U6") (pin "63") (pinfunction "PC6/T3_CH1_63") (pintype "passive"))
    )
    (net (code "40") (name "/SERVO2") (class "Default")
      (node (ref "R30") (pin "3") (pinfunction "3_3") (pintype "passive"))
      (node (ref "U6") (pin "64") (pinfunction "PC7/T3_CH2_64") (pintype "passive"))
    )
    (net (code "41") (name "/SERVO3") (class "Default")
      (node (ref "R30") (pin "2") (pinfunction "2_2") (pintype "passive"))
      (node (ref "U6") (pin "65") (pinfunction "PC8/T3_CH3_65") (pintype "passive"))
    )
    (net (code "42") (name "/SERVO4") (class "Default")
      (node (ref "R30") (pin "1") (pinfunction "1_1") (pintype "passive"))
      (node (ref "U6") (pin "66") (pinfunction "PC9/T3_CH4_66") (pintype "passive"))
    )
    (net (code "43") (name "/SWDCLK") (class "Default")
      (node (ref "H6") (pin "3") (pinfunction "3_3") (pintype "passive"))
      (node (ref "U6") (pin "76") (pinfunction "PA14/CLK_76") (pintype "passive"))
    )
    (net (code "44") (name "/SWDIO") (class "Default")
      (node (ref "H6") (pin "4") (pinfunction "4_4") (pintype "passive"))
      (node (ref "U6") (pin "72") (pinfunction "PA13/IO_72") (pintype "passive"))
    )
    (net (code "45") (name "/UART1_RX") (class "Default")
      (node (ref "CN7") (pin "4") (pinfunction "4_4") (pintype "passive"))
      (node (ref "J5") (pin "1") (pinfunction "1_1") (pintype "passive"))
      (node (ref "Q1") (pin "3") (pinfunction "3_3") (pintype "passive"))
      (node (ref "R26") (pin "1") (pinfunction "1_1") (pintype "passive"))
      (node (ref "U6") (pin "69") (pinfunction "PA10/U1_RX_69") (pintype "passive"))
    )
    (net (code "46") (name "/UART1_TX") (class "Default")
      (node (ref "CN7") (pin "3") (pinfunction "3_3") (pintype "passive"))
      (node (ref "J5") (pin "2") (pinfunction "2_2") (pintype "passive"))
      (node (ref "U6") (pin "68") (pinfunction "PA9/U1_TX_68") (pintype "passive"))
    )
    (net (code "47") (name "/UART2_RX") (class "Default")
      (node (ref "J4") (pin "1") (pinfunction "1_1") (pintype "passive"))
      (node (ref "U6") (pin "26") (pinfunction "PA3/U2_RX_26") (pintype "passive"))
    )
    (net (code "48") (name "/UART2_TX") (class "Default")
      (node (ref "H2") (pin "4") (pinfunction "4_4") (pintype "passive"))
      (node (ref "J4") (pin "2") (pinfunction "2_2") (pintype "passive"))
      (node (ref "U6") (pin "25") (pinfunction "PA2/U2_TX_25") (pintype "passive"))
    )
    (net (code "49") (name "/UART3_RX") (class "Default")
      (node (ref "CN1") (pin "3") (pinfunction "3_3") (pintype "passive"))
      (node (ref "J3") (pin "1") (pinfunction "1_1") (pintype "passive"))
      (node (ref "U6") (pin "34") (pinfunction "PC5/U3_RX_34") (pintype "passive"))
    )
    (net (code "50") (name "/UART3_TX") (class "Default")
      (node (ref "CN1") (pin "4") (pinfunction "4_4") (pintype "passive"))
      (node (ref "J3") (pin "2") (pinfunction "2_2") (pintype "passive"))
      (node (ref "U6") (pin "33") (pinfunction "PC4/U3_TX_33") (pintype "passive"))
    )
    (net (code "51") (name "/UART4_RX") (class "Default")
      (node (ref "CN3") (pin "2") (pinfunction "2_2") (pintype "passive"))
      (node (ref "J1") (pin "1") (pinfunction "1_1") (pintype "passive"))
      (node (ref "U11") (pin "2") (pinfunction "2_2") (pintype "passive"))
      (node (ref "U6") (pin "24") (pinfunction "PA1/U4_RX_24") (pintype "passive"))
    )
    (net (code "52") (name "/UART4_TX") (class "Default")
      (node (ref "J1") (pin "2") (pinfunction "2_2") (pintype "passive"))
      (node (ref "U6") (pin "23") (pinfunction "PA0/U4_TX_23") (pintype "passive"))
    )
    (net (code "53") (name "/UART8_RX") (class "Default")
      (node (ref "CN8") (pin "2") (pinfunction "2_2") (pintype "passive"))
      (node (ref "H3") (pin "3") (pinfunction "3_3") (pintype "passive"))
      (node (ref "U6") (pin "18") (pinfunction "PC3/U8_RX_18") (pintype "passive"))
    )
    (net (code "54") (name "/UART8_TX") (class "Default")
      (node (ref "CN8") (pin "1") (pinfunction "1_1") (pintype "passive"))
      (node (ref "H3") (pin "4") (pinfunction "4_4") (pintype "passive"))
      (node (ref "U6") (pin "17") (pinfunction "PC2/U8_TX_17") (pintype "passive"))
    )
    (net (code "55") (name "/VBAT_ADC") (class "Default")
      (node (ref "C22") (pin "2") (pinfunction "2_2") (pintype "passive"))
      (node (ref "R15") (pin "1") (pinfunction "1_1") (pintype "passive"))
      (node (ref "R16") (pin "2") (pinfunction "2_2") (pintype "passive"))
      (node (ref "U6") (pin "35") (pinfunction "PB0_35") (pintype "passive"))
    )
    (net (code "56") (name "/VBUS") (class "Default")
      (node (ref "D1") (pin "1") (pinfunction "A_1") (pintype "passive"))
      (node (ref "USB1") (pin "A4") (pinfunction "VBUS_A4") (pintype "passive"))
      (node (ref "USB1") (pin "A9") (pinfunction "VBUS_A9") (pintype "passive"))
      (node (ref "USB1") (pin "B4") (pinfunction "VBUS_B4") (pintype "passive"))
      (node (ref "USB1") (pin "B9") (pinfunction "VBUS_B9") (pintype "passive"))
    )
    (net (code "57") (name "3V3-IMU") (class "Default")
      (node (ref "C21") (pin "2") (pinfunction "2_2") (pintype "passive"))
      (node (ref "C23") (pin "2") (pinfunction "2_2") (pintype "passive"))
      (node (ref "C24") (pin "2") (pinfunction "2_2") (pintype "passive"))
      (node (ref "C3") (pin "2") (pinfunction "2_2") (pintype "passive"))
      (node (ref "C36") (pin "1") (pinfunction "1_1") (pintype "passive"))
      (node (ref "C37") (pin "1") (pinfunction "1_1") (pintype "passive"))
      (node (ref "C39") (pin "1") (pinfunction "1_1") (pintype "passive"))
      (node (ref "C4") (pin "2") (pinfunction "2_2") (pintype "passive"))
      (node (ref "R34") (pin "2") (pinfunction "2_2") (pintype "passive"))
      (node (ref "R35") (pin "2") (pinfunction "2_2") (pintype "passive"))
      (node (ref "R36") (pin "2") (pinfunction "2_2") (pintype "passive"))
      (node (ref "SDO1") (pin "5") (pinfunction "VDDIO_5") (pintype "passive"))
      (node (ref "SDO1") (pin "8") (pinfunction "VDD_8") (pintype "passive"))
      (node (ref "U12") (pin "5") (pinfunction "OUT_5") (pintype "passive"))
      (node (ref "U4") (pin "13") (pinfunction "VDD_13") (pintype "passive"))
      (node (ref "U4") (pin "8") (pinfunction "VDDIO_8") (pintype "passive"))
    )
    (net (code "58") (name "GND") (class "Default")
      (node (ref "C1") (pin "1") (pinfunction "1_1") (pintype "passive"))
      (node (ref "C10") (pin "1") (pinfunction "1_1") (pintype "passive"))
      (node (ref "C11") (pin "1") (pinfunction "1_1") (pintype "passive"))
      (node (ref "C12") (pin "1") (pinfunction "1_1") (pintype "passive"))
      (node (ref "C13") (pin "1") (pinfunction "1_1") (pintype "passive"))
      (node (ref "C14") (pin "1") (pinfunction "1_1") (pintype "passive"))
      (node (ref "C15") (pin "1") (pinfunction "1_1") (pintype "passive"))
      (node (ref "C16") (pin "1") (pinfunction "1_1") (pintype "passive"))
      (node (ref "C17") (pin "1") (pinfunction "1_1") (pintype "passive"))
      (node (ref "C18") (pin "1") (pinfunction "1_1") (pintype "passive"))
      (node (ref "C19") (pin "1") (pinfunction "1_1") (pintype "passive"))
      (node (ref "C2") (pin "1") (pinfunction "1_1") (pintype "passive"))
      (node (ref "C20") (pin "1") (pinfunction "1_1") (pintype "passive"))
      (node (ref "C21") (pin "1") (pinfunction "1_1") (pintype "passive"))
      (node (ref "C22") (pin "1") (pinfunction "1_1") (pintype "passive"))
      (node (ref "C23") (pin "1") (pinfunction "1_1") (pintype "passive"))
      (node (ref "C24") (pin "1") (pinfunction "1_1") (pintype "passive"))
      (node (ref "C25") (pin "1") (pinfunction "1_1") (pintype "passive"))
      (node (ref "C28") (pin "1") (pinfunction "1_1") (pintype "passive"))
      (node (ref "C29") (pin "1") (pinfunction "1_1") (pintype "passive"))
      (node (ref "C3") (pin "1") (pinfunction "1_1") (pintype "passive"))
      (node (ref "C30") (pin "1") (pinfunction "1_1") (pintype "passive"))
      (node (ref "C31") (pin "1") (pinfunction "1_1") (pintype "passive"))
      (node (ref "C32") (pin "1") (pinfunction "1_1") (pintype "passive"))
      (node (ref "C33") (pin "1") (pinfunction "1_1") (pintype "passive"))
      (node (ref "C35") (pin "2") (pinfunction "2_2") (pintype "passive"))
      (node (ref "C36") (pin "2") (pinfunction "2_2") (pintype "passive"))
      (node (ref "C37") (pin "2") (pinfunction "2_2") (pintype "passive"))
      (node (ref "C38") (pin "1") (pinfunction "1_1") (pintype "passive"))
      (node (ref "C39") (pin "2") (pinfunction "2_2") (pintype "passive"))
      (node (ref "C4") (pin "1") (pinfunction "1_1") (pintype "passive"))
      (node (ref "C7") (pin "1") (pinfunction "1_1") (pintype "passive"))
      (node (ref "C8") (pin "1") (pinfunction "1_1") (pintype "passive"))
      (node (ref "C9") (pin "1") (pinfunction "1_1") (pintype "passive"))
      (node (ref "CN1") (pin "2") (pinfunction "2_2") (pintype "passive"))
      (node (ref "CN1") (pin "5") (pinfunction "5_5") (pintype "passive"))
      (node (ref "CN1") (pin "7") (pinfunction "7_7") (pintype "passive"))
      (node (ref "CN1") (pin "8") (pinfunction "8_8") (pintype "passive"))
      (node (ref "CN2") (pin "1") (pinfunction "1_1") (pintype "passive"))
      (node (ref "CN2") (pin "4") (pinfunction "4_4") (pintype "passive"))
      (node (ref "CN2") (pin "5") (pinfunction "5_5") (pintype "passive"))
      (node (ref "CN3") (pin "10") (pinfunction "10_10") (pintype "passive"))
      (node (ref "CN3") (pin "7") (pinfunction "7_7") (pintype "passive"))
      (node (ref "CN3") (pin "9") (pinfunction "9_9") (pintype "passive"))
      (node (ref "CN4") (pin "1") (pinfunction "1_1") (pintype "passive"))
      (node (ref "CN4") (pin "4") (pinfunction "4_4") (pintype "passive"))
      (node (ref "CN4") (pin "5") (pinfunction "5_5") (pintype "passive"))
      (node (ref "CN5") (pin "1") (pinfunction "1_1") (pintype "passive"))
      (node (ref "CN5") (pin "4") (pinfunction "4_4") (pintype "passive"))
      (node (ref "CN5") (pin "5") (pinfunction "5_5") (pintype "passive"))
      (node (ref "CN6") (pin "1") (pinfunction "1_1") (pintype "passive"))
      (node (ref "CN6") (pin "4") (pinfunction "4_4") (pintype "passive"))
      (node (ref "CN6") (pin "5") (pinfunction "5_5") (pintype "passive"))
      (node (ref "CN7") (pin "2") (pinfunction "2_2") (pintype "passive"))
      (node (ref "CN7") (pin "7") (pinfunction "7_7") (pintype "passive"))
      (node (ref "CN7") (pin "8") (pinfunction "8_8") (pintype "passive"))
      (node (ref "CN8") (pin "3") (pinfunction "3_3") (pintype "passive"))
      (node (ref "CN8") (pin "5") (pinfunction "5_5") (pintype "passive"))
      (node (ref "CN8") (pin "6") (pinfunction "6_6") (pintype "passive"))
      (node (ref "D3") (pin "2") (pinfunction "2_2") (pintype "passive"))
      (node (ref "H1") (pin "3") (pinfunction "3_3") (pintype "passive"))
      (node (ref "H2") (pin "2") (pinfunction "2_2") (pintype "passive"))
      (node (ref "H3") (pin "2") (pinfunction "2_2") (pintype "passive"))
      (node (ref "H6") (pin "2") (pinfunction "2_2") (pintype "passive"))
      (node (ref "H7") (pin "3") (pinfunction "3_3") (pintype "passive"))
      (node (ref "LED1") (pin "2") (pinfunction "2_2") (pintype "passive"))
      (node (ref "LED2") (pin "2") (pinfunction "2_2") (pintype "passive"))
      (node (ref "Q1") (pin "2") (pinfunction "2_2") (pintype "passive"))
      (node (ref "Q2") (pin "2") (pinfunction "2_2") (pintype "passive"))
      (node (ref "R13") (pin "1") (pinfunction "1_1") (pintype "passive"))
      (node (ref "R14") (pin "1") (pinfunction "1_1") (pintype "passive"))
      (node (ref "R16") (pin "1") (pinfunction "1_1") (pintype "passive"))
      (node (ref "R17") (pin "2") (pinfunction "2_2") (pintype "passive"))
      (node (ref "R20") (pin "1") (pinfunction "1_1") (pintype "passive"))
      (node (ref "R22") (pin "1") (pinfunction "1_1") (pintype "passive"))
      (node (ref "R32") (pin "1") (pinfunction "1_1") (pintype "passive"))
      (node (ref "R33") (pin "1") (pinfunction "1_1") (pintype "passive"))
      (node (ref "SDO1") (pin "6") (pinfunction "GND_6") (pintype "passive"))
      (node (ref "SDO1") (pin "7") (pinfunction "RESV_7") (pintype "passive"))
      (node (ref "U1") (pin "2") (pinfunction "GND_2") (pintype "passive"))
      (node (ref "U10") (pin "4") (pinfunction "GND_4") (pintype "passive"))
      (node (ref "U10") (pin "9") (pinfunction "EP_9") (pintype "passive"))
      (node (ref "U11") (pin "11") (pinfunction "11_11") (pintype "passive"))
      (node (ref "U11") (pin "12") (pinfunction "12_12") (pintype "passive"))
      (node (ref "U11") (pin "7") (pinfunction "7_7") (pintype "passive"))
      (node (ref "U11") (pin "8") (pinfunction "8_8") (pintype "passive"))
      (node (ref "U12") (pin "2") (pinfunction "GND_2") (pintype "passive"))
      (node (ref "U2") (pin "5") (pinfunction "GND_5") (pintype "passive"))
      (node (ref "U3") (pin "5") (pinfunction "GND_5") (pintype "passive"))
      (node (ref "U4") (pin "18") (pinfunction "GND_18") (pintype "passive"))
      (node (ref "U4") (pin "20") (pinfunction "RESV_20") (pintype "passive"))
      (node (ref "U4") (pin "25") (pinfunction "EP_25") (pintype "passive"))
      (node (ref "U5") (pin "2") (pinfunction "2_2") (pintype "passive"))
      (node (ref "U6") (pin "10") (pinfunction "VSS_10") (pintype "passive"))
      (node (ref "U6") (pin "20") (pinfunction "VSSA/VREF-_20") (pintype "passive"))
      (node (ref "U6") (pin "27") (pinfunction "VSS_27") (pintype "passive"))
      (node (ref "U6") (pin "74") (pinfunction "VSS_74") (pintype "passive"))
      (node (ref "U6") (pin "99") (pinfunction "VSS_99") (pintype "passive"))
      (node (ref "U7") (pin "1") (pinfunction "GND_1") (pintype "passive"))
      (node (ref "U7") (pin "5") (pinfunction "SDO_5") (pintype "passive"))
      (node (ref "U7") (pin "7") (pinfunction "GND_7") (pintype "passive"))
      (node (ref "U8") (pin "2") (pinfunction "D_2") (pintype "passive"))
      (node (ref "U8") (pin "4") (pinfunction "D_4") (pintype "passive"))
      (node (ref "U9") (pin "20") (pinfunction "AGND_20") (pintype "passive"))
      (node (ref "U9") (pin "23") (pinfunction "PGND_23") (pintype "passive"))
      (node (ref "U9") (pin "4") (pinfunction "DGND_4") (pintype "passive"))
      (node (ref "USB1") (pin "25") (pinfunction "EH_25") (pintype "passive"))
      (node (ref "USB1") (pin "26") (pinfunction "EH_26") (pintype "passive"))
      (node (ref "USB1") (pin "27") (pinfunction "EH_27") (pintype "passive"))
      (node (ref "USB1") (pin "28") (pinfunction "EH_28") (pintype "passive"))
      (node (ref "USB1") (pin "A1") (pinfunction "GND_A1") (pintype "passive"))
      (node (ref "USB1") (pin "A12") (pinfunction "GND_A12") (pintype "passive"))
      (node (ref "USB1") (pin "B1") (pinfunction "GND_B1") (pintype "passive"))
      (node (ref "USB1") (pin "B12") (pinfunction "GND_B12") (pintype "passive"))
    )
    (net (code "59") (name "Net-(C5-Pad1)") (class "Default")
      (node (ref "C5") (pin "1") (pinfunction "1_1") (pintype "passive"))
      (node (ref "R1") (pin "2") (pinfunction "2_2") (pintype "passive"))
    )
    (net (code "60") (name "Net-(C6-Pad1)") (class "Default")
      (node (ref "C6") (pin "1") (pinfunction "1_1") (pintype "passive"))
      (node (ref "R2") (pin "2") (pinfunction "2_2") (pintype "passive"))
    )
    (net (code "61") (name "Net-(C26-Pad1)") (class "Default")
      (node (ref "C26") (pin "1") (pinfunction "1_1") (pintype "passive"))
      (node (ref "C27") (pin "1") (pinfunction "1_1") (pintype "passive"))
      (node (ref "R19") (pin "1") (pinfunction "1_1") (pintype "passive"))
    )
    (net (code "62") (name "Net-(CN3-Pad3)") (class "Default")
      (node (ref "CN3") (pin "3") (pinfunction "3_3") (pintype "passive"))
      (node (ref "R30") (pin "8") (pinfunction "8_8") (pintype "passive"))
    )
    (net (code "63") (name "Net-(CN3-Pad4)") (class "Default")
      (node (ref "CN3") (pin "4") (pinfunction "4_4") (pintype "passive"))
      (node (ref "R30") (pin "7") (pinfunction "7_7") (pintype "passive"))
    )
    (net (code "64") (name "Net-(CN3-Pad5)") (class "Default")
      (node (ref "CN3") (pin "5") (pinfunction "5_5") (pintype "passive"))
      (node (ref "R30") (pin "6") (pinfunction "6_6") (pintype "passive"))
    )
    (net (code "65") (name "Net-(CN3-Pad6)") (class "Default")
      (node (ref "CN3") (pin "6") (pinfunction "6_6") (pintype "passive"))
      (node (ref "R30") (pin "5") (pinfunction "5_5") (pintype "passive"))
    )
    (net (code "66") (name "Net-(D2-A)") (class "Default")
      (node (ref "C15") (pin "2") (pinfunction "2_2") (pintype "passive"))
      (node (ref "C16") (pin "2") (pinfunction "2_2") (pintype "passive"))
      (node (ref "D2") (pin "1") (pinfunction "A_1") (pintype "passive"))
      (node (ref "L2") (pin "2") (pinfunction "2_2") (pintype "passive"))
      (node (ref "R12") (pin "2") (pinfunction "2_2") (pintype "passive"))
    )
    (net (code "67") (name "Net-(LED1-Pad1)") (class "Default")
      (node (ref "LED1") (pin "1") (pinfunction "1_1") (pintype "passive"))
      (node (ref "R27") (pin "1") (pinfunction "1_1") (pintype "passive"))
    )
    (net (code "68") (name "Net-(LED2-Pad1)") (class "Default")
      (node (ref "LED2") (pin "1") (pinfunction "1_1") (pintype "passive"))
      (node (ref "R28") (pin "1") (pinfunction "1_1") (pintype "passive"))
    )
    (net (code "69") (name "Net-(Q2-Pad1)") (class "Default")
      (node (ref "Q2") (pin "1") (pinfunction "1_1") (pintype "passive"))
      (node (ref "R31") (pin "2") (pinfunction "2_2") (pintype "passive"))
    )
    (net (code "70") (name "Net-(R11-Pad2)") (class "Default")
      (node (ref "R11") (pin "2") (pinfunction "2_2") (pintype "passive"))
      (node (ref "R12") (pin "1") (pinfunction "1_1") (pintype "passive"))
      (node (ref "R14") (pin "2") (pinfunction "2_2") (pintype "passive"))
    )
    (net (code "71") (name "Net-(R13-Pad2)") (class "Default")
      (node (ref "R13") (pin "2") (pinfunction "2_2") (pintype "passive"))
      (node (ref "R8") (pin "2") (pinfunction "2_2") (pintype "passive"))
      (node (ref "R9") (pin "1") (pinfunction "1_1") (pintype "passive"))
    )
    (net (code "72") (name "Net-(R29-Pad5)") (class "Default")
      (node (ref "R29") (pin "5") (pinfunction "5_5") (pintype "passive"))
      (node (ref "U11") (pin "6") (pinfunction "6_6") (pintype "passive"))
    )
    (net (code "73") (name "Net-(R29-Pad6)") (class "Default")
      (node (ref "R29") (pin "6") (pinfunction "6_6") (pintype "passive"))
      (node (ref "U11") (pin "5") (pinfunction "5_5") (pintype "passive"))
    )
    (net (code "74") (name "Net-(R29-Pad7)") (class "Default")
      (node (ref "R29") (pin "7") (pinfunction "7_7") (pintype "passive"))
      (node (ref "U11") (pin "4") (pinfunction "4_4") (pintype "passive"))
    )
    (net (code "75") (name "Net-(R29-Pad8)") (class "Default")
      (node (ref "R29") (pin "8") (pinfunction "8_8") (pintype "passive"))
      (node (ref "U11") (pin "3") (pinfunction "3_3") (pintype "passive"))
    )
    (net (code "76") (name "Net-(U2-BST)") (class "Default")
      (node (ref "R1") (pin "1") (pinfunction "1_1") (pintype "passive"))
      (node (ref "U2") (pin "4") (pinfunction "BST_4") (pintype "passive"))
    )
    (net (code "77") (name "Net-(U2-EN)") (class "Default")
      (node (ref "R3") (pin "1") (pinfunction "1_1") (pintype "passive"))
      (node (ref "U2") (pin "3") (pinfunction "EN_3") (pintype "passive"))
    )
    (net (code "78") (name "Net-(U2-FB)") (class "Default")
      (node (ref "R8") (pin "1") (pinfunction "1_1") (pintype "passive"))
      (node (ref "U2") (pin "1") (pinfunction "FB_1") (pintype "passive"))
    )
    (net (code "79") (name "Net-(U2-PG)") (class "Default")
      (node (ref "R7") (pin "2") (pinfunction "2_2") (pintype "passive"))
      (node (ref "U2") (pin "8") (pinfunction "PG_8") (pintype "passive"))
    )
    (net (code "80") (name "Net-(U2-SW)") (class "Default")
      (node (ref "C5") (pin "2") (pinfunction "2_2") (pintype "passive"))
      (node (ref "L1") (pin "1") (pinfunction "1_1") (pintype "passive"))
      (node (ref "U2") (pin "6") (pinfunction "SW_6") (pintype "passive"))
    )
    (net (code "81") (name "Net-(U2-VCC)") (class "Default")
      (node (ref "C9") (pin "2") (pinfunction "2_2") (pintype "passive"))
      (node (ref "R7") (pin "1") (pinfunction "1_1") (pintype "passive"))
      (node (ref "U2") (pin "2") (pinfunction "VCC_2") (pintype "passive"))
    )
    (net (code "82") (name "Net-(U3-BST)") (class "Default")
      (node (ref "R2") (pin "1") (pinfunction "1_1") (pintype "passive"))
      (node (ref "U3") (pin "4") (pinfunction "BST_4") (pintype "passive"))
    )
    (net (code "83") (name "Net-(U3-EN)") (class "Default")
      (node (ref "R4") (pin "1") (pinfunction "1_1") (pintype "passive"))
      (node (ref "U3") (pin "3") (pinfunction "EN_3") (pintype "passive"))
    )
    (net (code "84") (name "Net-(U3-FB)") (class "Default")
      (node (ref "R11") (pin "1") (pinfunction "1_1") (pintype "passive"))
      (node (ref "U3") (pin "1") (pinfunction "FB_1") (pintype "passive"))
    )
    (net (code "85") (name "Net-(U3-PG)") (class "Default")
      (node (ref "R10") (pin "2") (pinfunction "2_2") (pintype "passive"))
      (node (ref "U3") (pin "8") (pinfunction "PG_8") (pintype "passive"))
    )
    (net (code "86") (name "Net-(U3-SW)") (class "Default")
      (node (ref "C6") (pin "2") (pinfunction "2_2") (pintype "passive"))
      (node (ref "L2") (pin "1") (pinfunction "1_1") (pintype "passive"))
      (node (ref "U3") (pin "6") (pinfunction "SW_6") (pintype "passive"))
    )
    (net (code "87") (name "Net-(U3-VCC)") (class "Default")
      (node (ref "C14") (pin "2") (pinfunction "2_2") (pintype "passive"))
      (node (ref "R10") (pin "1") (pinfunction "1_1") (pintype "passive"))
      (node (ref "U3") (pin "2") (pinfunction "VCC_2") (pintype "passive"))
    )
    (net (code "88") (name "Net-(U4-FSYNC)") (class "Default")
      (node (ref "R32") (pin "2") (pinfunction "2_2") (pintype "passive"))
      (node (ref "U4") (pin "11") (pinfunction "FSYNC_11") (pintype "passive"))
    )
    (net (code "89") (name "Net-(U4-REGOUT)") (class "Default")
      (node (ref "C38") (pin "2") (pinfunction "2_2") (pintype "passive"))
      (node (ref "U4") (pin "10") (pinfunction "REGOUT_10") (pintype "passive"))
    )
    (net (code "90") (name "Net-(U6-NRST)") (class "Default")
      (node (ref "R18") (pin "1") (pinfunction "1_1") (pintype "passive"))
      (node (ref "U6") (pin "14") (pinfunction "NRST_14") (pintype "passive"))
    )
    (net (code "91") (name "Net-(U6-PB2{slash}BOOT1)") (class "Default")
      (node (ref "R20") (pin "2") (pinfunction "2_2") (pintype "passive"))
      (node (ref "U6") (pin "37") (pinfunction "PB2/BOOT1_37") (pintype "passive"))
    )
    (net (code "92") (name "Net-(U8-OSC1)") (class "Default")
      (node (ref "U8") (pin "1") (pinfunction "OSC1_1") (pintype "passive"))
      (node (ref "U9") (pin "5") (pinfunction "CLKIN_5") (pintype "passive"))
    )
    (net (code "93") (name "Net-(U8-OSC2)") (class "Default")
      (node (ref "U8") (pin "3") (pinfunction "OSC2_3") (pintype "passive"))
      (node (ref "U9") (pin "6") (pinfunction "XFB_6") (pintype "passive"))
    )
    (net (code "94") (name "Net-(U9-RESET)") (class "Default")
      (node (ref "R23") (pin "1") (pinfunction "1_1") (pintype "passive"))
      (node (ref "U9") (pin "19") (pinfunction "RESET_19") (pintype "passive"))
    )
    (net (code "95") (name "Net-(U9-SAG)") (class "Default")
      (node (ref "C27") (pin "2") (pinfunction "2_2") (pintype "passive"))
      (node (ref "U9") (pin "25") (pinfunction "SAG_25") (pintype "passive"))
    )
    (net (code "96") (name "Net-(U9-VIN)") (class "Default")
      (node (ref "C34") (pin "1") (pinfunction "1_1") (pintype "passive"))
      (node (ref "U9") (pin "22") (pinfunction "VIN_22") (pintype "passive"))
    )
    (net (code "97") (name "Net-(U9-VOUT)") (class "Default")
      (node (ref "C26") (pin "2") (pinfunction "2_2") (pintype "passive"))
      (node (ref "U9") (pin "26") (pinfunction "VOUT_26") (pintype "passive"))
    )
    (net (code "98") (name "VBAT") (class "Default")
      (node (ref "C12") (pin "2") (pinfunction "2_2") (pintype "passive"))
      (node (ref "C13") (pin "2") (pinfunction "2_2") (pintype "passive"))
      (node (ref "C7") (pin "2") (pinfunction "2_2") (pintype "passive"))
      (node (ref "C8") (pin "2") (pinfunction "2_2") (pintype "passive"))
      (node (ref "CN3") (pin "8") (pinfunction "8_8") (pintype "passive"))
      (node (ref "D3") (pin "1") (pinfunction "1_1") (pintype "passive"))
      (node (ref "R15") (pin "2") (pinfunction "2_2") (pintype "passive"))
      (node (ref "R3") (pin "2") (pinfunction "2_2") (pintype "passive"))
      (node (ref "R4") (pin "2") (pinfunction "2_2") (pintype "passive"))
      (node (ref "U11") (pin "10") (pinfunction "10_10") (pintype "passive"))
      (node (ref "U11") (pin "9") (pinfunction "9_9") (pintype "passive"))
      (node (ref "U2") (pin "7") (pinfunction "IN_7") (pintype "passive"))
      (node (ref "U3") (pin "7") (pinfunction "IN_7") (pintype "passive"))
    )
    (net (code "99") (name "VDD") (class "Default")
      (node (ref "C19") (pin "2") (pinfunction "2_2") (pintype "passive"))
      (node (ref "C20") (pin "2") (pinfunction "2_2") (pintype "passive"))
      (node (ref "C25") (pin "2") (pinfunction "2_2") (pintype "passive"))
      (node (ref "C28") (pin "2") (pinfunction "2_2") (pintype "passive"))
      (node (ref "C29") (pin "2") (pinfunction "2_2") (pintype "passive"))
      (node (ref "C30") (pin "2") (pinfunction "2_2") (pintype "passive"))
      (node (ref "C31") (pin "2") (pinfunction "2_2") (pintype "passive"))
      (node (ref "C32") (pin "2") (pinfunction "2_2") (pintype "passive"))
      (node (ref "C33") (pin "2") (pinfunction "2_2") (pintype "passive"))
      (node (ref "C35") (pin "1") (pinfunction "1_1") (pintype "passive"))
      (node (ref "H6") (pin "1") (pinfunction "1_1") (pintype "passive"))
      (node (ref "R18") (pin "2") (pinfunction "2_2") (pintype "passive"))
      (node (ref "R24") (pin "2") (pinfunction "2_2") (pintype "passive"))
      (node (ref "R25") (pin "2") (pinfunction "2_2") (pintype "passive"))
      (node (ref "R26") (pin "2") (pinfunction "2_2") (pintype "passive"))
      (node (ref "SW1") (pin "2") (pinfunction "2_2") (pintype "passive"))
      (node (ref "U1") (pin "5") (pinfunction "OUT_5") (pintype "passive"))
      (node (ref "U10") (pin "3") (pinfunction "#WP/IO2_3") (pintype "passive"))
      (node (ref "U10") (pin "7") (pinfunction "#HOLD/IO3_7") (pintype "passive"))
      (node (ref "U10") (pin "8") (pinfunction "VCC_8") (pintype "passive"))
      (node (ref "U6") (pin "100") (pinfunction "VDD_100") (pintype "passive"))
      (node (ref "U6") (pin "11") (pinfunction "VDD_11") (pintype "passive"))
      (node (ref "U6") (pin "21") (pinfunction "VREF+_21") (pintype "passive"))
      (node (ref "U6") (pin "22") (pinfunction "VDDA_22") (pintype "passive"))
      (node (ref "U6") (pin "28") (pinfunction "VDD_28") (pintype "passive"))
      (node (ref "U6") (pin "50") (pinfunction "VDD_50") (pintype "passive"))
      (node (ref "U6") (pin "6") (pinfunction "VBAT_6") (pintype "passive"))
      (node (ref "U6") (pin "75") (pinfunction "VDD_75") (pintype "passive"))
      (node (ref "U7") (pin "2") (pinfunction "CSB_2") (pintype "passive"))
      (node (ref "U7") (pin "6") (pinfunction "VDDIO_6") (pintype "passive"))
      (node (ref "U7") (pin "8") (pinfunction "VDD_8") (pintype "passive"))
    )
    (net (code "100") (name "unconnected-(CN3-Pad1)") (class "Default")
      (node (ref "CN3") (pin "1") (pinfunction "1_1") (pintype "passive+no_connect"))
    )
    (net (code "101") (name "unconnected-(SDO1-RESV-Pad2)") (class "Default")
      (node (ref "SDO1") (pin "2") (pinfunction "RESV_2") (pintype "passive+no_connect"))
    )
    (net (code "102") (name "unconnected-(SDO1-RESV-Pad3)") (class "Default")
      (node (ref "SDO1") (pin "3") (pinfunction "RESV_3") (pintype "passive+no_connect"))
    )
    (net (code "103") (name "unconnected-(SDO1-RESV-Pad10)") (class "Default")
      (node (ref "SDO1") (pin "10") (pinfunction "RESV_10") (pintype "passive+no_connect"))
    )
    (net (code "104") (name "unconnected-(SDO1-RESV-Pad11)") (class "Default")
      (node (ref "SDO1") (pin "11") (pinfunction "RESV_11") (pintype "passive+no_connect"))
    )
    (net (code "105") (name "unconnected-(SW1-Pad3)") (class "Default")
      (node (ref "SW1") (pin "3") (pinfunction "3_3") (pintype "passive+no_connect"))
    )
    (net (code "106") (name "unconnected-(SW1-Pad4)") (class "Default")
      (node (ref "SW1") (pin "4") (pinfunction "4_4") (pintype "passive+no_connect"))
    )
    (net (code "107") (name "unconnected-(U1-BYP-Pad4)") (class "Default")
      (node (ref "U1") (pin "4") (pinfunction "BYP_4") (pintype "passive+no_connect"))
    )
    (net (code "108") (name "unconnected-(U4-AUX_CL-Pad7)") (class "Default")
      (node (ref "U4") (pin "7") (pinfunction "AUX_CL_7") (pintype "passive+no_connect"))
    )
    (net (code "109") (name "unconnected-(U4-AUX_DA-Pad21)") (class "Default")
      (node (ref "U4") (pin "21") (pinfunction "AUX_DA_21") (pintype "passive+no_connect"))
    )
    (net (code "110") (name "unconnected-(U4-NC-Pad1)") (class "Default")
      (node (ref "U4") (pin "1") (pinfunction "NC_1") (pintype "passive+no_connect"))
    )
    (net (code "111") (name "unconnected-(U4-NC-Pad2)") (class "Default")
      (node (ref "U4") (pin "2") (pinfunction "NC_2") (pintype "passive+no_connect"))
    )
    (net (code "112") (name "unconnected-(U4-NC-Pad3)") (class "Default")
      (node (ref "U4") (pin "3") (pinfunction "NC_3") (pintype "passive+no_connect"))
    )
    (net (code "113") (name "unconnected-(U4-NC-Pad4)") (class "Default")
      (node (ref "U4") (pin "4") (pinfunction "NC_4") (pintype "passive+no_connect"))
    )
    (net (code "114") (name "unconnected-(U4-NC-Pad5)") (class "Default")
      (node (ref "U4") (pin "5") (pinfunction "NC_5") (pintype "passive+no_connect"))
    )
    (net (code "115") (name "unconnected-(U4-NC-Pad6)") (class "Default")
      (node (ref "U4") (pin "6") (pinfunction "NC_6") (pintype "passive+no_connect"))
    )
    (net (code "116") (name "unconnected-(U4-NC-Pad14)") (class "Default")
      (node (ref "U4") (pin "14") (pinfunction "NC_14") (pintype "passive+no_connect"))
    )
    (net (code "117") (name "unconnected-(U4-NC-Pad15)") (class "Default")
      (node (ref "U4") (pin "15") (pinfunction "NC_15") (pintype "passive+no_connect"))
    )
    (net (code "118") (name "unconnected-(U4-NC-Pad16)") (class "Default")
      (node (ref "U4") (pin "16") (pinfunction "NC_16") (pintype "passive+no_connect"))
    )
    (net (code "119") (name "unconnected-(U4-NC-Pad17)") (class "Default")
      (node (ref "U4") (pin "17") (pinfunction "NC_17") (pintype "passive+no_connect"))
    )
    (net (code "120") (name "unconnected-(U4-RESV-Pad19)") (class "Default")
      (node (ref "U4") (pin "19") (pinfunction "RESV_19") (pintype "passive+no_connect"))
    )
    (net (code "121") (name "unconnected-(U6-NC-Pad19)") (class "Default")
      (node (ref "U6") (pin "19") (pinfunction "NC_19") (pintype "passive+no_connect"))
    )
    (net (code "122") (name "unconnected-(U6-PA8-Pad67)") (class "Default")
      (node (ref "U6") (pin "67") (pinfunction "PA8_67") (pintype "passive+no_connect"))
    )
    (net (code "123") (name "unconnected-(U6-PB3-Pad89)") (class "Default")
      (node (ref "U6") (pin "89") (pinfunction "PB3_89") (pintype "passive+no_connect"))
    )
    (net (code "124") (name "unconnected-(U6-PB4-Pad90)") (class "Default")
      (node (ref "U6") (pin "90") (pinfunction "PB4_90") (pintype "passive+no_connect"))
    )
    (net (code "125") (name "unconnected-(U6-PB5-Pad91)") (class "Default")
      (node (ref "U6") (pin "91") (pinfunction "PB5_91") (pintype "passive+no_connect"))
    )
    (net (code "126") (name "unconnected-(U6-PB12-Pad51)") (class "Default")
      (node (ref "U6") (pin "51") (pinfunction "PB12_51") (pintype "passive+no_connect"))
    )
    (net (code "127") (name "unconnected-(U6-PB13-Pad52)") (class "Default")
      (node (ref "U6") (pin "52") (pinfunction "PB13_52") (pintype "passive+no_connect"))
    )
    (net (code "128") (name "unconnected-(U6-PB14-Pad53)") (class "Default")
      (node (ref "U6") (pin "53") (pinfunction "PB14_53") (pintype "passive+no_connect"))
    )
    (net (code "129") (name "unconnected-(U6-PB15-Pad54)") (class "Default")
      (node (ref "U6") (pin "54") (pinfunction "PB15_54") (pintype "passive+no_connect"))
    )
    (net (code "130") (name "unconnected-(U6-PC13-Pad7)") (class "Default")
      (node (ref "U6") (pin "7") (pinfunction "PC13_7") (pintype "passive+no_connect"))
    )
    (net (code "131") (name "unconnected-(U6-PC14-Pad8)") (class "Default")
      (node (ref "U6") (pin "8") (pinfunction "PC14_8") (pintype "passive+no_connect"))
    )
    (net (code "132") (name "unconnected-(U6-PC15-Pad9)") (class "Default")
      (node (ref "U6") (pin "9") (pinfunction "PC15_9") (pintype "passive+no_connect"))
    )
    (net (code "133") (name "unconnected-(U6-PD0-Pad81)") (class "Default")
      (node (ref "U6") (pin "81") (pinfunction "PD0_81") (pintype "passive+no_connect"))
    )
    (net (code "134") (name "unconnected-(U6-PD2-Pad83)") (class "Default")
      (node (ref "U6") (pin "83") (pinfunction "PD2_83") (pintype "passive+no_connect"))
    )
    (net (code "135") (name "unconnected-(U6-PD7-Pad88)") (class "Default")
      (node (ref "U6") (pin "88") (pinfunction "PD7_88") (pintype "passive+no_connect"))
    )
    (net (code "136") (name "unconnected-(U6-PD8-Pad55)") (class "Default")
      (node (ref "U6") (pin "55") (pinfunction "PD8_55") (pintype "passive+no_connect"))
    )
    (net (code "137") (name "unconnected-(U6-PD9-Pad56)") (class "Default")
      (node (ref "U6") (pin "56") (pinfunction "PD9_56") (pintype "passive+no_connect"))
    )
    (net (code "138") (name "unconnected-(U6-PD10-Pad57)") (class "Default")
      (node (ref "U6") (pin "57") (pinfunction "PD10_57") (pintype "passive+no_connect"))
    )
    (net (code "139") (name "unconnected-(U6-PD11-Pad58)") (class "Default")
      (node (ref "U6") (pin "58") (pinfunction "PD11_58") (pintype "passive+no_connect"))
    )
    (net (code "140") (name "unconnected-(U6-PD12-Pad59)") (class "Default")
      (node (ref "U6") (pin "59") (pinfunction "PD12_59") (pintype "passive+no_connect"))
    )
    (net (code "141") (name "unconnected-(U6-PE0-Pad97)") (class "Default")
      (node (ref "U6") (pin "97") (pinfunction "PE0_97") (pintype "passive+no_connect"))
    )
    (net (code "142") (name "unconnected-(U6-PE1-Pad98)") (class "Default")
      (node (ref "U6") (pin "98") (pinfunction "PE1_98") (pintype "passive+no_connect"))
    )
    (net (code "143") (name "unconnected-(U6-PE2-Pad1)") (class "Default")
      (node (ref "U6") (pin "1") (pinfunction "PE2_1") (pintype "passive+no_connect"))
    )
    (net (code "144") (name "unconnected-(U6-PE3-Pad2)") (class "Default")
      (node (ref "U6") (pin "2") (pinfunction "PE3_2") (pintype "passive+no_connect"))
    )
    (net (code "145") (name "unconnected-(U6-PE4-Pad3)") (class "Default")
      (node (ref "U6") (pin "3") (pinfunction "PE4_3") (pintype "passive+no_connect"))
    )
    (net (code "146") (name "unconnected-(U6-PE5-Pad4)") (class "Default")
      (node (ref "U6") (pin "4") (pinfunction "PE5_4") (pintype "passive+no_connect"))
    )
    (net (code "147") (name "unconnected-(U6-PE6-Pad5)") (class "Default")
      (node (ref "U6") (pin "5") (pinfunction "PE6_5") (pintype "passive+no_connect"))
    )
    (net (code "148") (name "unconnected-(U6-PE7-Pad38)") (class "Default")
      (node (ref "U6") (pin "38") (pinfunction "PE7_38") (pintype "passive+no_connect"))
    )
    (net (code "149") (name "unconnected-(U6-PE8-Pad39)") (class "Default")
      (node (ref "U6") (pin "39") (pinfunction "PE8_39") (pintype "passive+no_connect"))
    )
    (net (code "150") (name "unconnected-(U6-PE9-Pad40)") (class "Default")
      (node (ref "U6") (pin "40") (pinfunction "PE9_40") (pintype "passive+no_connect"))
    )
    (net (code "151") (name "unconnected-(U6-PE10-Pad41)") (class "Default")
      (node (ref "U6") (pin "41") (pinfunction "PE10_41") (pintype "passive+no_connect"))
    )
    (net (code "152") (name "unconnected-(U6-PE11-Pad42)") (class "Default")
      (node (ref "U6") (pin "42") (pinfunction "PE11_42") (pintype "passive+no_connect"))
    )
    (net (code "153") (name "unconnected-(U6-PE12-Pad43)") (class "Default")
      (node (ref "U6") (pin "43") (pinfunction "PE12_43") (pintype "passive+no_connect"))
    )
    (net (code "154") (name "unconnected-(U6-PE13-Pad44)") (class "Default")
      (node (ref "U6") (pin "44") (pinfunction "PE13_44") (pintype "passive+no_connect"))
    )
    (net (code "155") (name "unconnected-(U6-PE14-Pad45)") (class "Default")
      (node (ref "U6") (pin "45") (pinfunction "PE14_45") (pintype "passive+no_connect"))
    )
    (net (code "156") (name "unconnected-(U6-PE15-Pad46)") (class "Default")
      (node (ref "U6") (pin "46") (pinfunction "PE15_46") (pintype "passive+no_connect"))
    )
    (net (code "157") (name "unconnected-(U6-PH2-Pad73)") (class "Default")
      (node (ref "U6") (pin "73") (pinfunction "PH2_73") (pintype "passive+no_connect"))
    )
    (net (code "158") (name "unconnected-(U6-PH3-Pad49)") (class "Default")
      (node (ref "U6") (pin "49") (pinfunction "PH3_49") (pintype "passive+no_connect"))
    )
    (net (code "159") (name "unconnected-(U9-CLKOUT-Pad7)") (class "Default")
      (node (ref "U9") (pin "7") (pinfunction "CLKOUT_7") (pintype "passive+no_connect"))
    )
    (net (code "160") (name "unconnected-(U9-HSYNC-Pad18)") (class "Default")
      (node (ref "U9") (pin "18") (pinfunction "HSYNC_18") (pintype "passive+no_connect"))
    )
    (net (code "161") (name "unconnected-(U9-LOS-Pad12)") (class "Default")
      (node (ref "U9") (pin "12") (pinfunction "LOS_12") (pintype "passive+no_connect"))
    )
    (net (code "162") (name "unconnected-(U9-NC-Pad1)") (class "Default")
      (node (ref "U9") (pin "1") (pinfunction "NC_1") (pintype "passive+no_connect"))
    )
    (net (code "163") (name "unconnected-(U9-NC-Pad2)") (class "Default")
      (node (ref "U9") (pin "2") (pinfunction "NC_2") (pintype "passive+no_connect"))
    )
    (net (code "164") (name "unconnected-(U9-NC-Pad13)") (class "Default")
      (node (ref "U9") (pin "13") (pinfunction "NC_13") (pintype "passive+no_connect"))
    )
    (net (code "165") (name "unconnected-(U9-NC-Pad14)") (class "Default")
      (node (ref "U9") (pin "14") (pinfunction "NC_14") (pintype "passive+no_connect"))
    )
    (net (code "166") (name "unconnected-(U9-NC-Pad15)") (class "Default")
      (node (ref "U9") (pin "15") (pinfunction "NC_15") (pintype "passive+no_connect"))
    )
    (net (code "167") (name "unconnected-(U9-NC-Pad16)") (class "Default")
      (node (ref "U9") (pin "16") (pinfunction "NC_16") (pintype "passive+no_connect"))
    )
    (net (code "168") (name "unconnected-(U9-NC-Pad27)") (class "Default")
      (node (ref "U9") (pin "27") (pinfunction "NC_27") (pintype "passive+no_connect"))
    )
    (net (code "169") (name "unconnected-(U9-NC-Pad28)") (class "Default")
      (node (ref "U9") (pin "28") (pinfunction "NC_28") (pintype "passive+no_connect"))
    )
    (net (code "170") (name "unconnected-(U9-VSYNC-Pad17)") (class "Default")
      (node (ref "U9") (pin "17") (pinfunction "VSYNC_17") (pintype "passive+no_connect"))
    )
    (net (code "171") (name "unconnected-(U12-BYP-Pad4)") (class "Default")
      (node (ref "U12") (pin "4") (pinfunction "BYP_4") (pintype "passive+no_connect"))
    )
    (net (code "172") (name "unconnected-(USB1-CC1-PadA5)") (class "Default")
      (node (ref "USB1") (pin "A5") (pinfunction "CC1_A5") (pintype "passive+no_connect"))
    )
    (net (code "173") (name "unconnected-(USB1-CC2-PadB5)") (class "Default")
      (node (ref "USB1") (pin "B5") (pinfunction "CC2_B5") (pintype "passive+no_connect"))
    )
    (net (code "174") (name "unconnected-(USB1-SUB1-PadA8)") (class "Default")
      (node (ref "USB1") (pin "A8") (pinfunction "SUB1_A8") (pintype "passive+no_connect"))
    )
    (net (code "175") (name "unconnected-(USB1-SUB2-PadB8)") (class "Default")
      (node (ref "USB1") (pin "B8") (pinfunction "SUB2_B8") (pintype "passive+no_connect"))
    )
  )
)
